# mmu6100.net
KiCad netlist of a schematic drawn in EAGLE
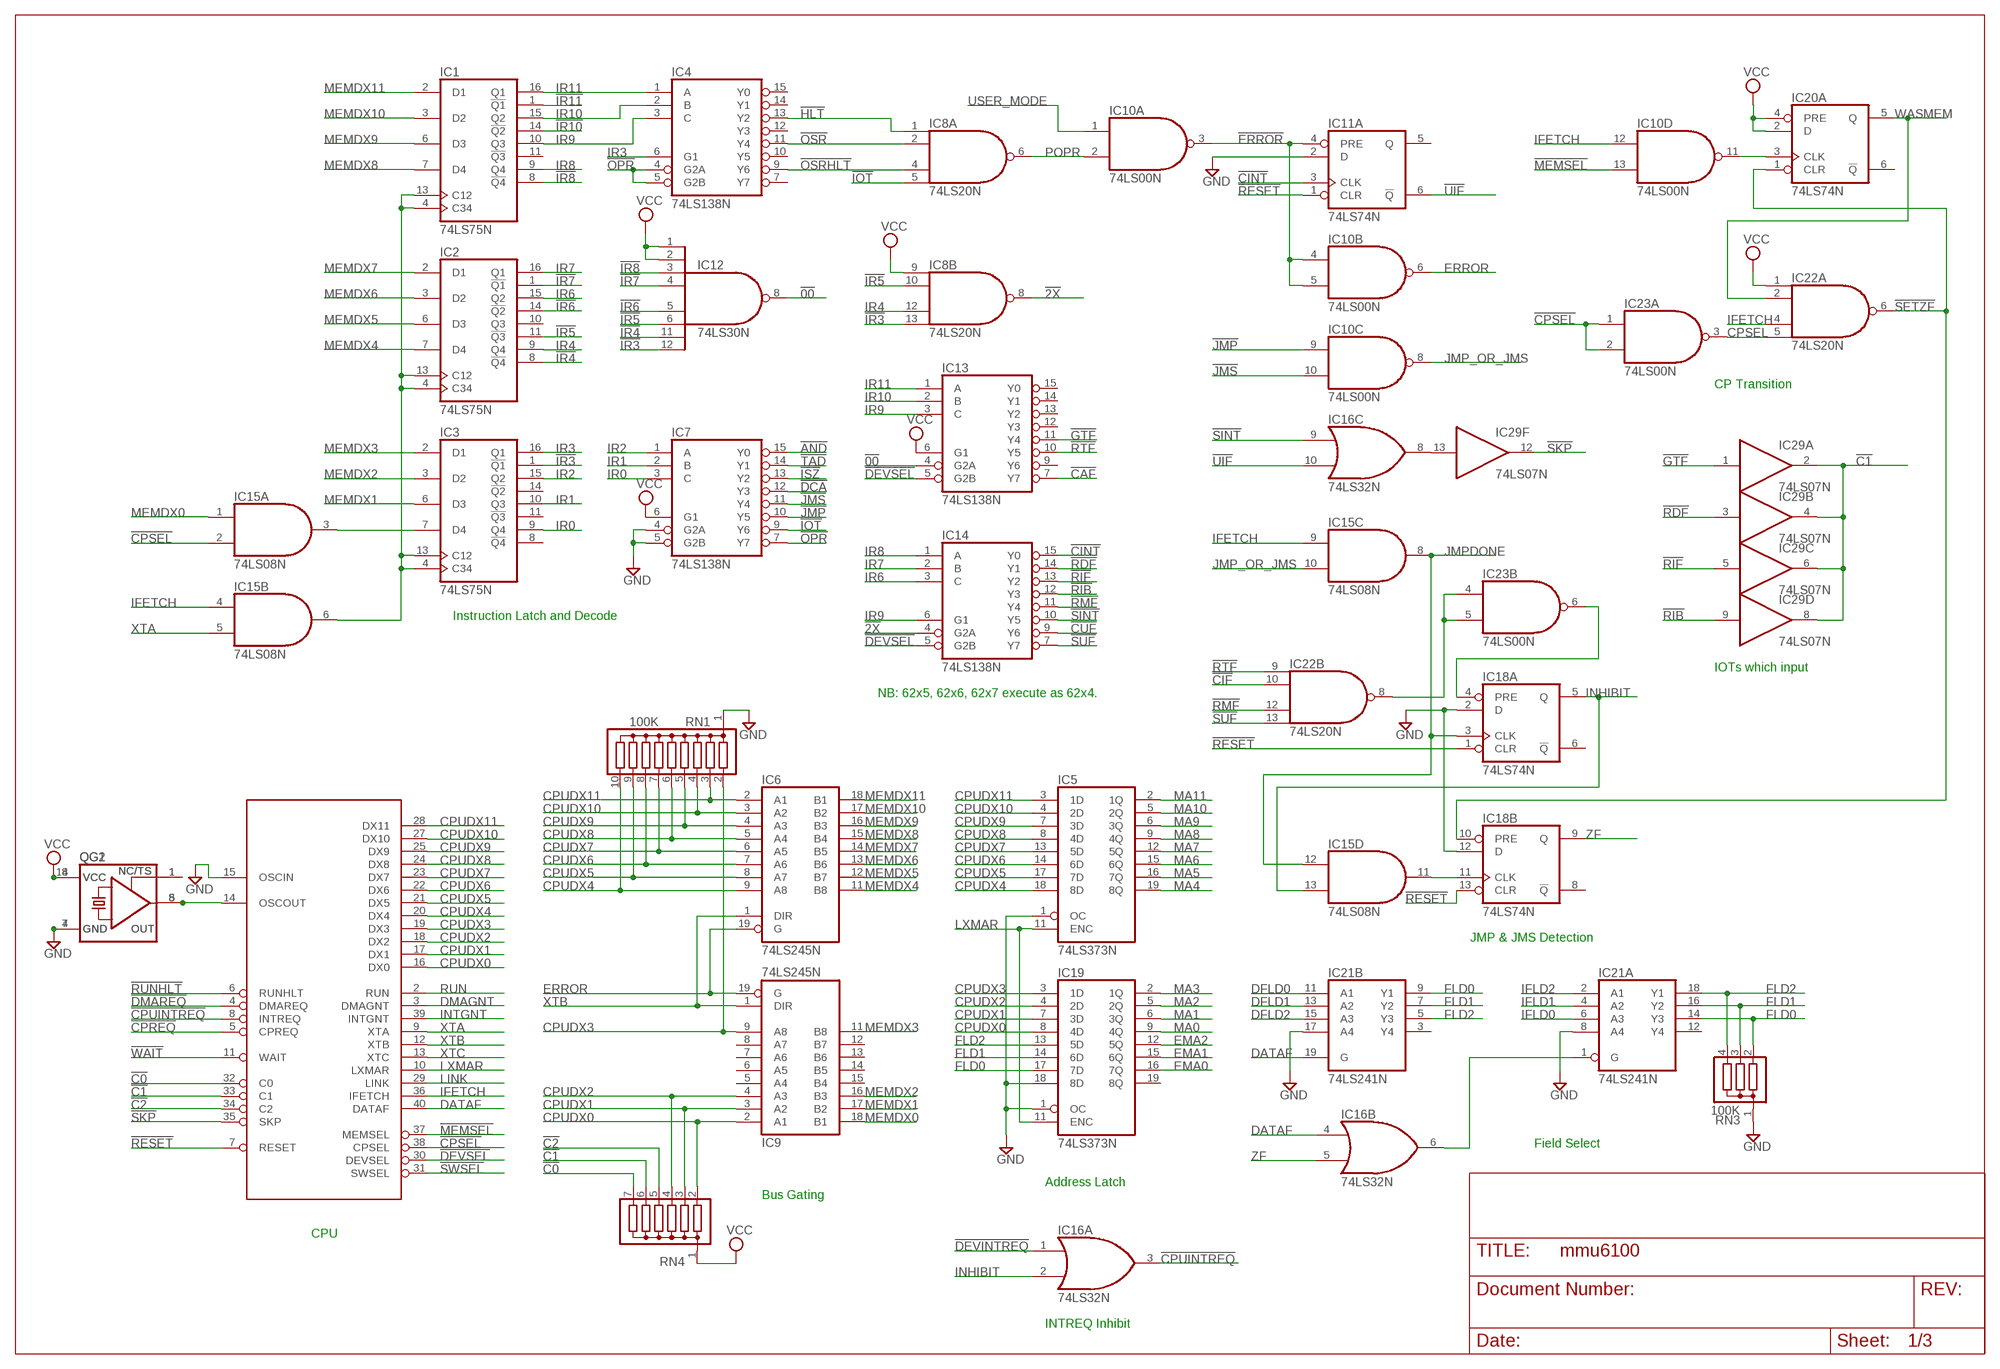
[diagram p0: schematic, sheet 1]
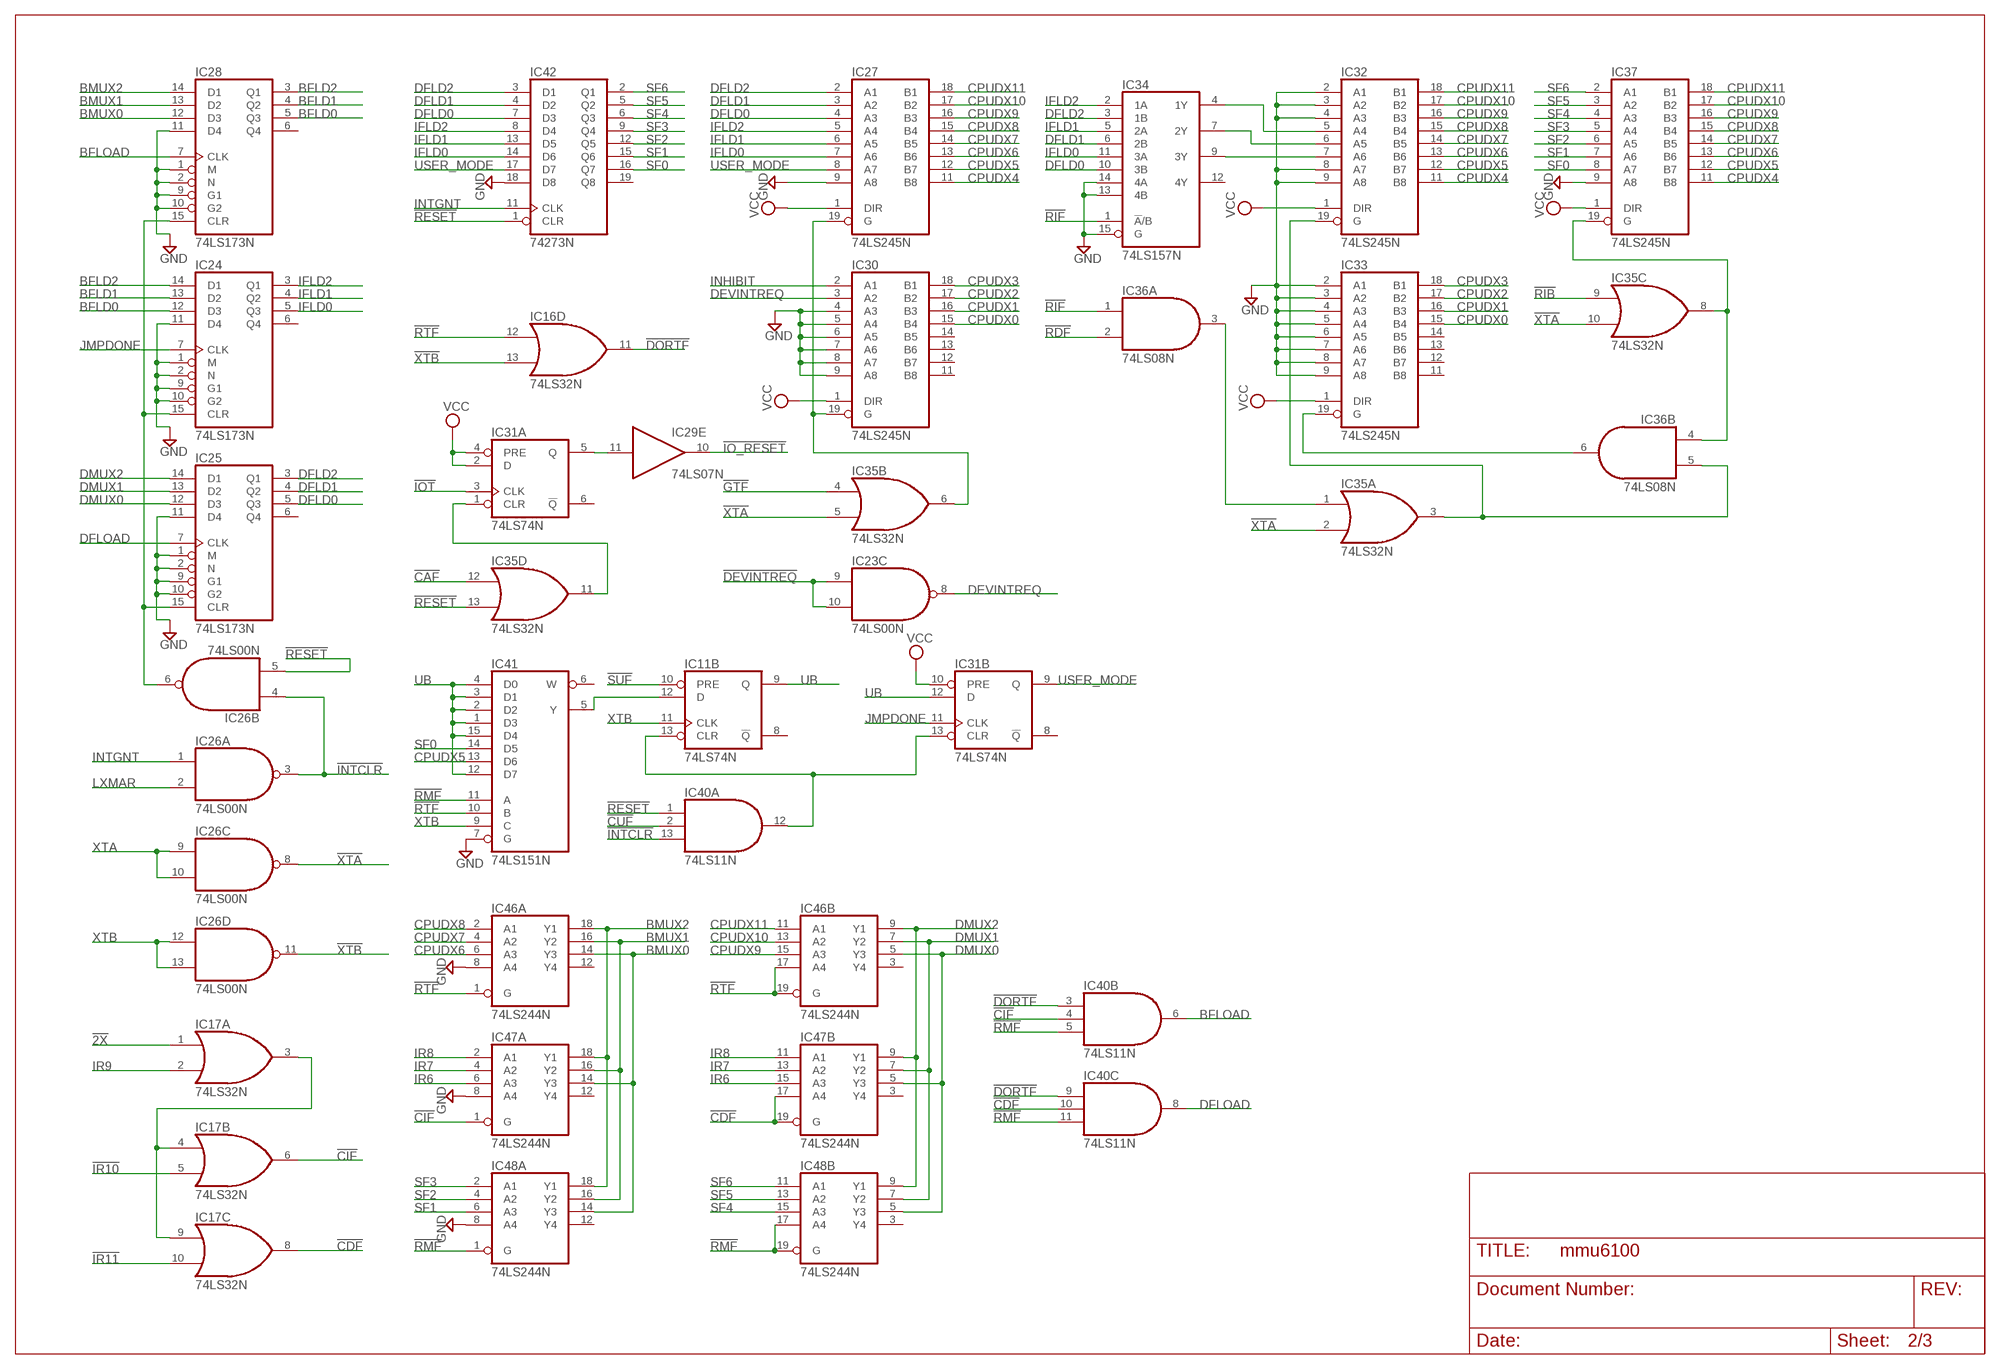
[diagram p1: schematic, sheet 2]
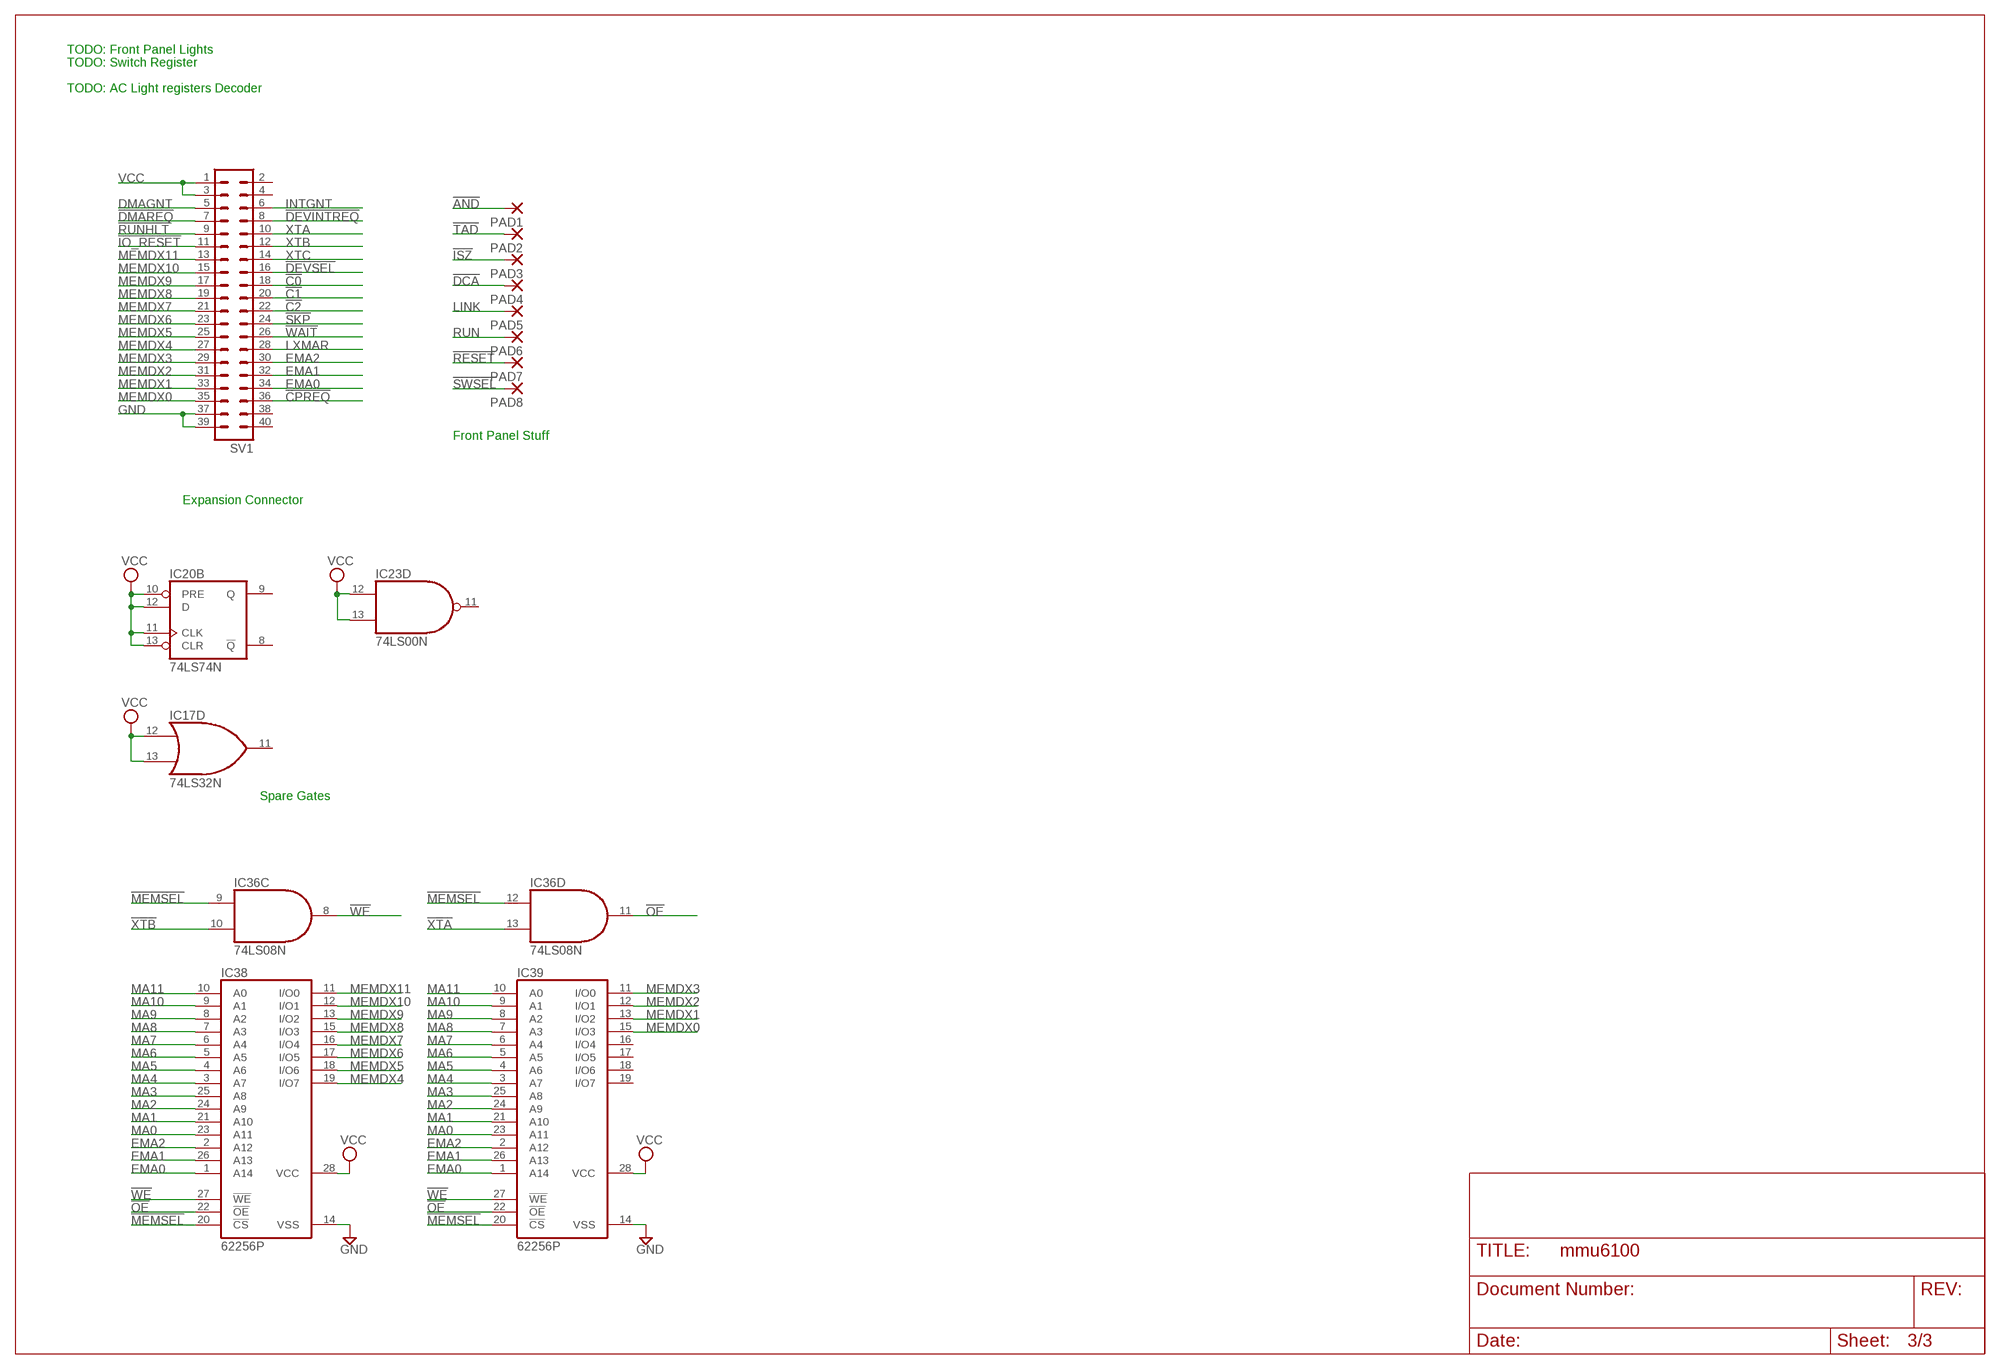
[diagram p2: schematic, sheet 3]

(export (version "E")
  (design (tool "Eeschema 10.0.6"))
  (components
    (comp (ref "IC17")
      (value "74LS32N")
      (footprint "eagle-import:DIL14")
      (libsource (lib "eagle-import") (part "7432NLS"))
    )
    (comp (ref "IC20")
      (value "74LS74N")
      (footprint "eagle-import:DIL14")
      (libsource (lib "eagle-import") (part "7474NLS"))
    )
    (comp (ref "IC23")
      (value "74LS00N")
      (footprint "eagle-import:DIL14")
      (libsource (lib "eagle-import") (part "7400NLS"))
    )
    (comp (ref "IC36")
      (value "74LS08N")
      (footprint "eagle-import:DIL14")
      (libsource (lib "eagle-import") (part "7408NLS"))
    )
    (comp (ref "IC38")
      (value "62256P")
      (footprint "eagle-import:DIL28-6")
      (libsource (lib "eagle-import") (part "62256P"))
    )
    (comp (ref "IC39")
      (value "62256P")
      (footprint "eagle-import:DIL28-6")
      (libsource (lib "eagle-import") (part "62256P"))
    )
    (comp (ref "PAD1")
      (value "2,15/1,0")
      (footprint "eagle-import:2,15_1,0")
      (libsource (lib "eagle-import") (part "2,15/1,0"))
    )
    (comp (ref "PAD2")
      (value "2,15/1,0")
      (footprint "eagle-import:2,15_1,0")
      (libsource (lib "eagle-import") (part "2,15/1,0"))
    )
    (comp (ref "PAD3")
      (value "2,15/1,0")
      (footprint "eagle-import:2,15_1,0")
      (libsource (lib "eagle-import") (part "2,15/1,0"))
    )
    (comp (ref "PAD4")
      (value "2,15/1,0")
      (footprint "eagle-import:2,15_1,0")
      (libsource (lib "eagle-import") (part "2,15/1,0"))
    )
    (comp (ref "PAD5")
      (value "2,15/1,0")
      (footprint "eagle-import:2,15_1,0")
      (libsource (lib "eagle-import") (part "2,15/1,0"))
    )
    (comp (ref "PAD6")
      (value "2,15/1,0")
      (footprint "eagle-import:2,15_1,0")
      (libsource (lib "eagle-import") (part "2,15/1,0"))
    )
    (comp (ref "PAD7")
      (value "2,15/1,0")
      (footprint "eagle-import:2,15_1,0")
      (libsource (lib "eagle-import") (part "2,15/1,0"))
    )
    (comp (ref "PAD8")
      (value "2,15/1,0")
      (footprint "eagle-import:2,15_1,0")
      (libsource (lib "eagle-import") (part "2,15/1,0"))
    )
    (comp (ref "SV1")
      (value "MA20-2")
      (footprint "eagle-import:MA20-2")
      (libsource (lib "eagle-import") (part "MA20-2"))
    )
    (comp (ref "IC11")
      (value "74LS74N")
      (footprint "eagle-import:DIL14")
      (libsource (lib "eagle-import") (part "7474NLS"))
    )
    (comp (ref "IC16")
      (value "74LS32N")
      (footprint "eagle-import:DIL14")
      (libsource (lib "eagle-import") (part "7432NLS"))
    )
    (comp (ref "IC24")
      (value "74LS173N")
      (footprint "eagle-import:DIL16")
      (libsource (lib "eagle-import") (part "74173NLS"))
    )
    (comp (ref "IC25")
      (value "74LS173N")
      (footprint "eagle-import:DIL16")
      (libsource (lib "eagle-import") (part "74173NLS"))
    )
    (comp (ref "IC26")
      (value "74LS00N")
      (footprint "eagle-import:DIL14")
      (libsource (lib "eagle-import") (part "7400NLS"))
    )
    (comp (ref "IC27")
      (value "74LS245N")
      (footprint "eagle-import:DIL20")
      (libsource (lib "eagle-import") (part "74245NLS"))
    )
    (comp (ref "IC28")
      (value "74LS173N")
      (footprint "eagle-import:DIL16")
      (libsource (lib "eagle-import") (part "74173NLS"))
    )
    (comp (ref "IC29")
      (value "74LS07N")
      (footprint "eagle-import:DIL14")
      (libsource (lib "eagle-import") (part "7407NLS"))
    )
    (comp (ref "IC30")
      (value "74LS245N")
      (footprint "eagle-import:DIL20")
      (libsource (lib "eagle-import") (part "74245NLS"))
    )
    (comp (ref "IC31")
      (value "74LS74N")
      (footprint "eagle-import:DIL14")
      (libsource (lib "eagle-import") (part "7474NLS"))
    )
    (comp (ref "IC32")
      (value "74LS245N")
      (footprint "eagle-import:DIL20")
      (libsource (lib "eagle-import") (part "74245NLS"))
    )
    (comp (ref "IC33")
      (value "74LS245N")
      (footprint "eagle-import:DIL20")
      (libsource (lib "eagle-import") (part "74245NLS"))
    )
    (comp (ref "IC34")
      (value "74LS157N")
      (footprint "eagle-import:DIL16")
      (libsource (lib "eagle-import") (part "74157NLS"))
    )
    (comp (ref "IC35")
      (value "74LS32N")
      (footprint "eagle-import:DIL14")
      (libsource (lib "eagle-import") (part "7432NLS"))
    )
    (comp (ref "IC37")
      (value "74LS245N")
      (footprint "eagle-import:DIL20")
      (libsource (lib "eagle-import") (part "74245NLS"))
    )
    (comp (ref "IC40")
      (value "74LS11N")
      (footprint "eagle-import:DIL14")
      (libsource (lib "eagle-import") (part "7411NLS"))
    )
    (comp (ref "IC41")
      (value "74LS151N")
      (footprint "eagle-import:DIL16")
      (libsource (lib "eagle-import") (part "74151NLS"))
    )
    (comp (ref "IC42")
      (value "74273N")
      (footprint "eagle-import:DIL20")
      (libsource (lib "eagle-import") (part "74273N"))
    )
    (comp (ref "IC46")
      (value "74LS244N")
      (footprint "eagle-import:DIL20")
      (libsource (lib "eagle-import") (part "74244NLS"))
    )
    (comp (ref "IC47")
      (value "74LS244N")
      (footprint "eagle-import:DIL20")
      (libsource (lib "eagle-import") (part "74244NLS"))
    )
    (comp (ref "IC48")
      (value "74LS244N")
      (footprint "eagle-import:DIL20")
      (libsource (lib "eagle-import") (part "74244NLS"))
    )
    (comp (ref "CPU")
      (value "IM6100")
      (footprint "eagle-import:DIL40")
      (libsource (lib "eagle-import") (part "IM6100"))
    )
    (comp (ref "IC1")
      (value "74LS75N")
      (footprint "eagle-import:DIL16")
      (libsource (lib "eagle-import") (part "7475NLS"))
    )
    (comp (ref "IC2")
      (value "74LS75N")
      (footprint "eagle-import:DIL16")
      (libsource (lib "eagle-import") (part "7475NLS"))
    )
    (comp (ref "IC3")
      (value "74LS75N")
      (footprint "eagle-import:DIL16")
      (libsource (lib "eagle-import") (part "7475NLS"))
    )
    (comp (ref "IC4")
      (value "74LS138N")
      (footprint "eagle-import:DIL16")
      (libsource (lib "eagle-import") (part "74138NLS"))
    )
    (comp (ref "IC5")
      (value "74LS373N")
      (footprint "eagle-import:DIL20")
      (libsource (lib "eagle-import") (part "74373NLS"))
    )
    (comp (ref "IC6")
      (value "74LS245N")
      (footprint "eagle-import:DIL20")
      (libsource (lib "eagle-import") (part "74245NLS"))
    )
    (comp (ref "IC7")
      (value "74LS138N")
      (footprint "eagle-import:DIL16")
      (libsource (lib "eagle-import") (part "74138NLS"))
    )
    (comp (ref "IC8")
      (value "74LS20N")
      (footprint "eagle-import:DIL14")
      (libsource (lib "eagle-import") (part "7420NLS"))
    )
    (comp (ref "IC9")
      (value "74LS245N")
      (footprint "eagle-import:DIL20")
      (libsource (lib "eagle-import") (part "74245NLS"))
    )
    (comp (ref "IC10")
      (value "74LS00N")
      (footprint "eagle-import:DIL14")
      (libsource (lib "eagle-import") (part "7400NLS"))
    )
    (comp (ref "IC12")
      (value "74LS30N")
      (footprint "eagle-import:DIL14")
      (libsource (lib "eagle-import") (part "7430NLS"))
    )
    (comp (ref "IC13")
      (value "74LS138N")
      (footprint "eagle-import:DIL16")
      (libsource (lib "eagle-import") (part "74138NLS"))
    )
    (comp (ref "IC14")
      (value "74LS138N")
      (footprint "eagle-import:DIL16")
      (libsource (lib "eagle-import") (part "74138NLS"))
    )
    (comp (ref "IC15")
      (value "74LS08N")
      (footprint "eagle-import:DIL14")
      (libsource (lib "eagle-import") (part "7408NLS"))
    )
    (comp (ref "IC18")
      (value "74LS74N")
      (footprint "eagle-import:DIL14")
      (libsource (lib "eagle-import") (part "7474NLS"))
    )
    (comp (ref "IC19")
      (value "74LS373N")
      (footprint "eagle-import:DIL20")
      (libsource (lib "eagle-import") (part "74373NLS"))
    )
    (comp (ref "IC21")
      (value "74LS241N")
      (footprint "eagle-import:DIL20")
      (libsource (lib "eagle-import") (part "74241NLS"))
    )
    (comp (ref "IC22")
      (value "74LS20N")
      (footprint "eagle-import:DIL14")
      (libsource (lib "eagle-import") (part "7420NLS"))
    )
    (comp (ref "QG1")
      (value "XO-8")
      (footprint "eagle-import:DIL08S")
      (libsource (lib "eagle-import") (part "XO-8"))
    )
    (comp (ref "QG2")
      (value "XO-14")
      (footprint "eagle-import:DIL14S")
      (libsource (lib "eagle-import") (part "XO-14"))
    )
    (comp (ref "RN1")
      (value "100K")
      (footprint "eagle-import:SIL10")
      (libsource (lib "eagle-import") (part "G09R"))
    )
    (comp (ref "RN3")
      (value "100K")
      (footprint "eagle-import:SIL4")
      (libsource (lib "eagle-import") (part "G03R"))
    )
    (comp (ref "RN4")
      (value "G06R")
      (footprint "eagle-import:SIL7")
      (libsource (lib "eagle-import") (part "G06R"))
    )
  )
  (nets
    (net (code "1") (name "BFLD0") (class "Default")
      (node (ref "IC24") (pin "12") (pinfunction "D3_12") (pintype "input"))
      (node (ref "IC28") (pin "5") (pinfunction "Q3_5") (pintype "tri_state"))
    )
    (net (code "2") (name "BFLD1") (class "Default")
      (node (ref "IC24") (pin "13") (pinfunction "D2_13") (pintype "input"))
      (node (ref "IC28") (pin "4") (pinfunction "Q2_4") (pintype "tri_state"))
    )
    (net (code "3") (name "BFLD2") (class "Default")
      (node (ref "IC24") (pin "14") (pinfunction "D1_14") (pintype "input"))
      (node (ref "IC28") (pin "3") (pinfunction "Q1_3") (pintype "tri_state"))
    )
    (net (code "4") (name "BFLOAD") (class "Default")
      (node (ref "IC28") (pin "7") (pinfunction "CLK_7") (pintype "input"))
      (node (ref "IC40") (pin "6") (pinfunction "O_6") (pintype "output"))
    )
    (net (code "5") (name "BMUX0") (class "Default")
      (node (ref "IC28") (pin "12") (pinfunction "D3_12") (pintype "input"))
      (node (ref "IC46") (pin "14") (pinfunction "Y3_14") (pintype "tri_state"))
      (node (ref "IC47") (pin "14") (pinfunction "Y3_14") (pintype "tri_state"))
      (node (ref "IC48") (pin "14") (pinfunction "Y3_14") (pintype "tri_state"))
    )
    (net (code "6") (name "BMUX1") (class "Default")
      (node (ref "IC28") (pin "13") (pinfunction "D2_13") (pintype "input"))
      (node (ref "IC46") (pin "16") (pinfunction "Y2_16") (pintype "tri_state"))
      (node (ref "IC47") (pin "16") (pinfunction "Y2_16") (pintype "tri_state"))
      (node (ref "IC48") (pin "16") (pinfunction "Y2_16") (pintype "tri_state"))
    )
    (net (code "7") (name "BMUX2") (class "Default")
      (node (ref "IC28") (pin "14") (pinfunction "D1_14") (pintype "input"))
      (node (ref "IC46") (pin "18") (pinfunction "Y1_18") (pintype "tri_state"))
      (node (ref "IC47") (pin "18") (pinfunction "Y1_18") (pintype "tri_state"))
      (node (ref "IC48") (pin "18") (pinfunction "Y1_18") (pintype "tri_state"))
    )
    (net (code "8") (name "CPSEL") (class "Default")
      (node (ref "IC22") (pin "5") (pinfunction "I3_5") (pintype "input"))
      (node (ref "IC23") (pin "3") (pinfunction "O_3") (pintype "output"))
    )
    (net (code "9") (name "CPUDX0") (class "Default")
      (node (ref "CPU") (pin "16") (pinfunction "DX0_16") (pintype "bidirectional"))
      (node (ref "IC19") (pin "8") (pinfunction "4D_8") (pintype "input"))
      (node (ref "IC30") (pin "15") (pinfunction "B4_15") (pintype "bidirectional"))
      (node (ref "IC33") (pin "15") (pinfunction "B4_15") (pintype "bidirectional"))
      (node (ref "IC9") (pin "2") (pinfunction "A1_2") (pintype "bidirectional"))
      (node (ref "RN4") (pin "2") (pinfunction "2_2") (pintype "passive"))
    )
    (net (code "10") (name "CPUDX1") (class "Default")
      (node (ref "CPU") (pin "17") (pinfunction "DX1_17") (pintype "bidirectional"))
      (node (ref "IC19") (pin "7") (pinfunction "3D_7") (pintype "input"))
      (node (ref "IC30") (pin "16") (pinfunction "B3_16") (pintype "bidirectional"))
      (node (ref "IC33") (pin "16") (pinfunction "B3_16") (pintype "bidirectional"))
      (node (ref "IC9") (pin "3") (pinfunction "A2_3") (pintype "bidirectional"))
      (node (ref "RN4") (pin "3") (pinfunction "3_3") (pintype "passive"))
    )
    (net (code "11") (name "CPUDX2") (class "Default")
      (node (ref "CPU") (pin "18") (pinfunction "DX2_18") (pintype "bidirectional"))
      (node (ref "IC19") (pin "4") (pinfunction "2D_4") (pintype "input"))
      (node (ref "IC30") (pin "17") (pinfunction "B2_17") (pintype "bidirectional"))
      (node (ref "IC33") (pin "17") (pinfunction "B2_17") (pintype "bidirectional"))
      (node (ref "IC9") (pin "4") (pinfunction "A3_4") (pintype "bidirectional"))
      (node (ref "RN4") (pin "4") (pinfunction "4_4") (pintype "passive"))
    )
    (net (code "12") (name "CPUDX3") (class "Default")
      (node (ref "CPU") (pin "19") (pinfunction "DX3_19") (pintype "bidirectional"))
      (node (ref "IC19") (pin "3") (pinfunction "1D_3") (pintype "input"))
      (node (ref "IC30") (pin "18") (pinfunction "B1_18") (pintype "bidirectional"))
      (node (ref "IC33") (pin "18") (pinfunction "B1_18") (pintype "bidirectional"))
      (node (ref "IC9") (pin "9") (pinfunction "A8_9") (pintype "bidirectional"))
      (node (ref "RN1") (pin "2") (pinfunction "2_2") (pintype "passive"))
    )
    (net (code "13") (name "CPUDX4") (class "Default")
      (node (ref "CPU") (pin "20") (pinfunction "DX4_20") (pintype "bidirectional"))
      (node (ref "IC27") (pin "11") (pinfunction "B8_11") (pintype "bidirectional"))
      (node (ref "IC32") (pin "11") (pinfunction "B8_11") (pintype "bidirectional"))
      (node (ref "IC37") (pin "11") (pinfunction "B8_11") (pintype "bidirectional"))
      (node (ref "IC5") (pin "18") (pinfunction "8D_18") (pintype "input"))
      (node (ref "IC6") (pin "9") (pinfunction "A8_9") (pintype "bidirectional"))
      (node (ref "RN1") (pin "10") (pinfunction "10_10") (pintype "passive"))
    )
    (net (code "14") (name "CPUDX5") (class "Default")
      (node (ref "CPU") (pin "21") (pinfunction "DX5_21") (pintype "bidirectional"))
      (node (ref "IC27") (pin "12") (pinfunction "B7_12") (pintype "bidirectional"))
      (node (ref "IC32") (pin "12") (pinfunction "B7_12") (pintype "bidirectional"))
      (node (ref "IC37") (pin "12") (pinfunction "B7_12") (pintype "bidirectional"))
      (node (ref "IC41") (pin "13") (pinfunction "D6_13") (pintype "input"))
      (node (ref "IC5") (pin "17") (pinfunction "7D_17") (pintype "input"))
      (node (ref "IC6") (pin "8") (pinfunction "A7_8") (pintype "bidirectional"))
      (node (ref "RN1") (pin "9") (pinfunction "9_9") (pintype "passive"))
    )
    (net (code "15") (name "CPUDX6") (class "Default")
      (node (ref "CPU") (pin "22") (pinfunction "DX6_22") (pintype "bidirectional"))
      (node (ref "IC27") (pin "13") (pinfunction "B6_13") (pintype "bidirectional"))
      (node (ref "IC32") (pin "13") (pinfunction "B6_13") (pintype "bidirectional"))
      (node (ref "IC37") (pin "13") (pinfunction "B6_13") (pintype "bidirectional"))
      (node (ref "IC46") (pin "6") (pinfunction "A3_6") (pintype "input"))
      (node (ref "IC5") (pin "14") (pinfunction "6D_14") (pintype "input"))
      (node (ref "IC6") (pin "7") (pinfunction "A6_7") (pintype "bidirectional"))
      (node (ref "RN1") (pin "8") (pinfunction "8_8") (pintype "passive"))
    )
    (net (code "16") (name "CPUDX7") (class "Default")
      (node (ref "CPU") (pin "23") (pinfunction "DX7_23") (pintype "bidirectional"))
      (node (ref "IC27") (pin "14") (pinfunction "B5_14") (pintype "bidirectional"))
      (node (ref "IC32") (pin "14") (pinfunction "B5_14") (pintype "bidirectional"))
      (node (ref "IC37") (pin "14") (pinfunction "B5_14") (pintype "bidirectional"))
      (node (ref "IC46") (pin "4") (pinfunction "A2_4") (pintype "input"))
      (node (ref "IC5") (pin "13") (pinfunction "5D_13") (pintype "input"))
      (node (ref "IC6") (pin "6") (pinfunction "A5_6") (pintype "bidirectional"))
      (node (ref "RN1") (pin "7") (pinfunction "7_7") (pintype "passive"))
    )
    (net (code "17") (name "CPUDX8") (class "Default")
      (node (ref "CPU") (pin "24") (pinfunction "DX8_24") (pintype "bidirectional"))
      (node (ref "IC27") (pin "15") (pinfunction "B4_15") (pintype "bidirectional"))
      (node (ref "IC32") (pin "15") (pinfunction "B4_15") (pintype "bidirectional"))
      (node (ref "IC37") (pin "15") (pinfunction "B4_15") (pintype "bidirectional"))
      (node (ref "IC46") (pin "2") (pinfunction "A1_2") (pintype "input"))
      (node (ref "IC5") (pin "8") (pinfunction "4D_8") (pintype "input"))
      (node (ref "IC6") (pin "5") (pinfunction "A4_5") (pintype "bidirectional"))
      (node (ref "RN1") (pin "6") (pinfunction "6_6") (pintype "passive"))
    )
    (net (code "18") (name "CPUDX9") (class "Default")
      (node (ref "CPU") (pin "25") (pinfunction "DX9_25") (pintype "bidirectional"))
      (node (ref "IC27") (pin "16") (pinfunction "B3_16") (pintype "bidirectional"))
      (node (ref "IC32") (pin "16") (pinfunction "B3_16") (pintype "bidirectional"))
      (node (ref "IC37") (pin "16") (pinfunction "B3_16") (pintype "bidirectional"))
      (node (ref "IC46") (pin "15") (pinfunction "A3_15") (pintype "input"))
      (node (ref "IC5") (pin "7") (pinfunction "3D_7") (pintype "input"))
      (node (ref "IC6") (pin "4") (pinfunction "A3_4") (pintype "bidirectional"))
      (node (ref "RN1") (pin "5") (pinfunction "5_5") (pintype "passive"))
    )
    (net (code "19") (name "CPUDX10") (class "Default")
      (node (ref "CPU") (pin "27") (pinfunction "DX10_27") (pintype "bidirectional"))
      (node (ref "IC27") (pin "17") (pinfunction "B2_17") (pintype "bidirectional"))
      (node (ref "IC32") (pin "17") (pinfunction "B2_17") (pintype "bidirectional"))
      (node (ref "IC37") (pin "17") (pinfunction "B2_17") (pintype "bidirectional"))
      (node (ref "IC46") (pin "13") (pinfunction "A2_13") (pintype "input"))
      (node (ref "IC5") (pin "4") (pinfunction "2D_4") (pintype "input"))
      (node (ref "IC6") (pin "3") (pinfunction "A2_3") (pintype "bidirectional"))
      (node (ref "RN1") (pin "4") (pinfunction "4_4") (pintype "passive"))
    )
    (net (code "20") (name "CPUDX11") (class "Default")
      (node (ref "CPU") (pin "28") (pinfunction "DX11_28") (pintype "bidirectional"))
      (node (ref "IC27") (pin "18") (pinfunction "B1_18") (pintype "bidirectional"))
      (node (ref "IC32") (pin "18") (pinfunction "B1_18") (pintype "bidirectional"))
      (node (ref "IC37") (pin "18") (pinfunction "B1_18") (pintype "bidirectional"))
      (node (ref "IC46") (pin "11") (pinfunction "A1_11") (pintype "input"))
      (node (ref "IC5") (pin "3") (pinfunction "1D_3") (pintype "input"))
      (node (ref "IC6") (pin "2") (pinfunction "A1_2") (pintype "bidirectional"))
      (node (ref "RN1") (pin "3") (pinfunction "3_3") (pintype "passive"))
    )
    (net (code "21") (name "DATAF") (class "Default")
      (node (ref "CPU") (pin "40") (pinfunction "DATAF_40") (pintype "output"))
      (node (ref "IC16") (pin "4") (pinfunction "I0_4") (pintype "input"))
      (node (ref "IC21") (pin "19") (pinfunction "G_19") (pintype "input"))
    )
    (net (code "22") (name "DEVINTREQ") (class "Default")
      (node (ref "IC23") (pin "8") (pinfunction "O_8") (pintype "output"))
      (node (ref "IC30") (pin "3") (pinfunction "A2_3") (pintype "bidirectional"))
    )
    (net (code "23") (name "DFLD0") (class "Default")
      (node (ref "IC21") (pin "11") (pinfunction "A1_11") (pintype "input"))
      (node (ref "IC25") (pin "5") (pinfunction "Q3_5") (pintype "tri_state"))
      (node (ref "IC27") (pin "4") (pinfunction "A3_4") (pintype "bidirectional"))
      (node (ref "IC34") (pin "10") (pinfunction "3B_10") (pintype "input"))
      (node (ref "IC42") (pin "7") (pinfunction "D3_7") (pintype "input"))
    )
    (net (code "24") (name "DFLD1") (class "Default")
      (node (ref "IC21") (pin "13") (pinfunction "A2_13") (pintype "input"))
      (node (ref "IC25") (pin "4") (pinfunction "Q2_4") (pintype "tri_state"))
      (node (ref "IC27") (pin "3") (pinfunction "A2_3") (pintype "bidirectional"))
      (node (ref "IC34") (pin "6") (pinfunction "2B_6") (pintype "input"))
      (node (ref "IC42") (pin "4") (pinfunction "D2_4") (pintype "input"))
    )
    (net (code "25") (name "DFLD2") (class "Default")
      (node (ref "IC21") (pin "15") (pinfunction "A3_15") (pintype "input"))
      (node (ref "IC25") (pin "3") (pinfunction "Q1_3") (pintype "tri_state"))
      (node (ref "IC27") (pin "2") (pinfunction "A1_2") (pintype "bidirectional"))
      (node (ref "IC34") (pin "3") (pinfunction "1B_3") (pintype "input"))
      (node (ref "IC42") (pin "3") (pinfunction "D1_3") (pintype "input"))
    )
    (net (code "26") (name "DFLOAD") (class "Default")
      (node (ref "IC25") (pin "7") (pinfunction "CLK_7") (pintype "input"))
      (node (ref "IC40") (pin "8") (pinfunction "O_8") (pintype "output"))
    )
    (net (code "27") (name "DMAGNT") (class "Default")
      (node (ref "CPU") (pin "3") (pinfunction "DMAGNT_3") (pintype "output"))
      (node (ref "SV1") (pin "5") (pinfunction "5_5") (pintype "passive"))
    )
    (net (code "28") (name "DMUX0") (class "Default")
      (node (ref "IC25") (pin "12") (pinfunction "D3_12") (pintype "input"))
      (node (ref "IC46") (pin "5") (pinfunction "Y3_5") (pintype "tri_state"))
      (node (ref "IC47") (pin "5") (pinfunction "Y3_5") (pintype "tri_state"))
      (node (ref "IC48") (pin "5") (pinfunction "Y3_5") (pintype "tri_state"))
    )
    (net (code "29") (name "DMUX1") (class "Default")
      (node (ref "IC25") (pin "13") (pinfunction "D2_13") (pintype "input"))
      (node (ref "IC46") (pin "7") (pinfunction "Y2_7") (pintype "tri_state"))
      (node (ref "IC47") (pin "7") (pinfunction "Y2_7") (pintype "tri_state"))
      (node (ref "IC48") (pin "7") (pinfunction "Y2_7") (pintype "tri_state"))
    )
    (net (code "30") (name "DMUX2") (class "Default")
      (node (ref "IC25") (pin "14") (pinfunction "D1_14") (pintype "input"))
      (node (ref "IC46") (pin "9") (pinfunction "Y1_9") (pintype "tri_state"))
      (node (ref "IC47") (pin "9") (pinfunction "Y1_9") (pintype "tri_state"))
      (node (ref "IC48") (pin "9") (pinfunction "Y1_9") (pintype "tri_state"))
    )
    (net (code "31") (name "EMA0") (class "Default")
      (node (ref "IC19") (pin "16") (pinfunction "7Q_16") (pintype "tri_state"))
      (node (ref "IC38") (pin "1") (pinfunction "A14_1") (pintype "input"))
      (node (ref "IC39") (pin "1") (pinfunction "A14_1") (pintype "input"))
      (node (ref "SV1") (pin "34") (pinfunction "34_34") (pintype "passive"))
    )
    (net (code "32") (name "EMA1") (class "Default")
      (node (ref "IC19") (pin "15") (pinfunction "6Q_15") (pintype "tri_state"))
      (node (ref "IC38") (pin "26") (pinfunction "A13_26") (pintype "input"))
      (node (ref "IC39") (pin "26") (pinfunction "A13_26") (pintype "input"))
      (node (ref "SV1") (pin "32") (pinfunction "32_32") (pintype "passive"))
    )
    (net (code "33") (name "EMA2") (class "Default")
      (node (ref "IC19") (pin "12") (pinfunction "5Q_12") (pintype "tri_state"))
      (node (ref "IC38") (pin "2") (pinfunction "A12_2") (pintype "input"))
      (node (ref "IC39") (pin "2") (pinfunction "A12_2") (pintype "input"))
      (node (ref "SV1") (pin "30") (pinfunction "30_30") (pintype "passive"))
    )
    (net (code "34") (name "ERROR") (class "Default")
      (node (ref "IC10") (pin "6") (pinfunction "O_6") (pintype "output"))
      (node (ref "IC6") (pin "19") (pinfunction "G_19") (pintype "input"))
      (node (ref "IC9") (pin "19") (pinfunction "G_19") (pintype "input"))
    )
    (net (code "35") (name "FLD0") (class "Default")
      (node (ref "IC19") (pin "17") (pinfunction "7D_17") (pintype "input"))
      (node (ref "IC21") (pin "14") (pinfunction "Y3_14") (pintype "tri_state"))
      (node (ref "IC21") (pin "9") (pinfunction "Y1_9") (pintype "tri_state"))
      (node (ref "RN3") (pin "2") (pinfunction "2_2") (pintype "passive"))
    )
    (net (code "36") (name "FLD1") (class "Default")
      (node (ref "IC19") (pin "14") (pinfunction "6D_14") (pintype "input"))
      (node (ref "IC21") (pin "16") (pinfunction "Y2_16") (pintype "tri_state"))
      (node (ref "IC21") (pin "7") (pinfunction "Y2_7") (pintype "tri_state"))
      (node (ref "RN3") (pin "3") (pinfunction "3_3") (pintype "passive"))
    )
    (net (code "37") (name "FLD2") (class "Default")
      (node (ref "IC19") (pin "13") (pinfunction "5D_13") (pintype "input"))
      (node (ref "IC21") (pin "18") (pinfunction "Y1_18") (pintype "tri_state"))
      (node (ref "IC21") (pin "5") (pinfunction "Y3_5") (pintype "tri_state"))
      (node (ref "RN3") (pin "4") (pinfunction "4_4") (pintype "passive"))
    )
    (net (code "38") (name "GND") (class "Default")
      (node (ref "CPU") (pin "15") (pinfunction "OSCIN_15") (pintype "input"))
      (node (ref "IC11") (pin "2") (pinfunction "D_2") (pintype "input"))
      (node (ref "IC18") (pin "12") (pinfunction "D_12") (pintype "input"))
      (node (ref "IC18") (pin "2") (pinfunction "D_2") (pintype "input"))
      (node (ref "IC19") (pin "1") (pinfunction "OC_1") (pintype "input"))
      (node (ref "IC19") (pin "18") (pinfunction "8D_18") (pintype "input"))
      (node (ref "IC21") (pin "17") (pinfunction "A4_17") (pintype "input"))
      (node (ref "IC21") (pin "8") (pinfunction "A4_8") (pintype "input"))
      (node (ref "IC24") (pin "1") (pinfunction "M_1") (pintype "input"))
      (node (ref "IC24") (pin "10") (pinfunction "G2_10") (pintype "input"))
      (node (ref "IC24") (pin "11") (pinfunction "D4_11") (pintype "input"))
      (node (ref "IC24") (pin "2") (pinfunction "N_2") (pintype "input"))
      (node (ref "IC24") (pin "9") (pinfunction "G1_9") (pintype "input"))
      (node (ref "IC25") (pin "1") (pinfunction "M_1") (pintype "input"))
      (node (ref "IC25") (pin "10") (pinfunction "G2_10") (pintype "input"))
      (node (ref "IC25") (pin "11") (pinfunction "D4_11") (pintype "input"))
      (node (ref "IC25") (pin "2") (pinfunction "N_2") (pintype "input"))
      (node (ref "IC25") (pin "9") (pinfunction "G1_9") (pintype "input"))
      (node (ref "IC27") (pin "9") (pinfunction "A8_9") (pintype "bidirectional"))
      (node (ref "IC28") (pin "1") (pinfunction "M_1") (pintype "input"))
      (node (ref "IC28") (pin "10") (pinfunction "G2_10") (pintype "input"))
      (node (ref "IC28") (pin "11") (pinfunction "D4_11") (pintype "input"))
      (node (ref "IC28") (pin "2") (pinfunction "N_2") (pintype "input"))
      (node (ref "IC28") (pin "9") (pinfunction "G1_9") (pintype "input"))
      (node (ref "IC30") (pin "4") (pinfunction "A3_4") (pintype "bidirectional"))
      (node (ref "IC30") (pin "5") (pinfunction "A4_5") (pintype "bidirectional"))
      (node (ref "IC30") (pin "6") (pinfunction "A5_6") (pintype "bidirectional"))
      (node (ref "IC30") (pin "7") (pinfunction "A6_7") (pintype "bidirectional"))
      (node (ref "IC30") (pin "8") (pinfunction "A7_8") (pintype "bidirectional"))
      (node (ref "IC30") (pin "9") (pinfunction "A8_9") (pintype "bidirectional"))
      (node (ref "IC32") (pin "2") (pinfunction "A1_2") (pintype "bidirectional"))
      (node (ref "IC32") (pin "3") (pinfunction "A2_3") (pintype "bidirectional"))
      (node (ref "IC32") (pin "4") (pinfunction "A3_4") (pintype "bidirectional"))
      (node (ref "IC32") (pin "8") (pinfunction "A7_8") (pintype "bidirectional"))
      (node (ref "IC32") (pin "9") (pinfunction "A8_9") (pintype "bidirectional"))
      (node (ref "IC33") (pin "2") (pinfunction "A1_2") (pintype "bidirectional"))
      (node (ref "IC33") (pin "3") (pinfunction "A2_3") (pintype "bidirectional"))
      (node (ref "IC33") (pin "4") (pinfunction "A3_4") (pintype "bidirectional"))
      (node (ref "IC33") (pin "5") (pinfunction "A4_5") (pintype "bidirectional"))
      (node (ref "IC33") (pin "6") (pinfunction "A5_6") (pintype "bidirectional"))
      (node (ref "IC33") (pin "7") (pinfunction "A6_7") (pintype "bidirectional"))
      (node (ref "IC33") (pin "8") (pinfunction "A7_8") (pintype "bidirectional"))
      (node (ref "IC33") (pin "9") (pinfunction "A8_9") (pintype "bidirectional"))
      (node (ref "IC34") (pin "13") (pinfunction "4B_13") (pintype "input"))
      (node (ref "IC34") (pin "14") (pinfunction "4A_14") (pintype "input"))
      (node (ref "IC34") (pin "15") (pinfunction "G_15") (pintype "input"))
      (node (ref "IC37") (pin "9") (pinfunction "A8_9") (pintype "bidirectional"))
      (node (ref "IC38") (pin "14") (pinfunction "VSS_14") (pintype "power_in"))
      (node (ref "IC39") (pin "14") (pinfunction "VSS_14") (pintype "power_in"))
      (node (ref "IC41") (pin "7") (pinfunction "G_7") (pintype "input"))
      (node (ref "IC42") (pin "18") (pinfunction "D8_18") (pintype "input"))
      (node (ref "IC46") (pin "8") (pinfunction "A4_8") (pintype "input"))
      (node (ref "IC47") (pin "8") (pinfunction "A4_8") (pintype "input"))
      (node (ref "IC48") (pin "8") (pinfunction "A4_8") (pintype "input"))
      (node (ref "IC5") (pin "1") (pinfunction "OC_1") (pintype "input"))
      (node (ref "IC7") (pin "4") (pinfunction "G2A_4") (pintype "input"))
      (node (ref "IC7") (pin "5") (pinfunction "G2B_5") (pintype "input"))
      (node (ref "QG1") (pin "4") (pinfunction "GND_4") (pintype "power_in"))
      (node (ref "QG2") (pin "7") (pinfunction "GND_7") (pintype "power_in"))
      (node (ref "RN1") (pin "1") (pinfunction "1_1") (pintype "passive"))
      (node (ref "RN3") (pin "1") (pinfunction "1_1") (pintype "passive"))
      (node (ref "SV1") (pin "37") (pinfunction "37_37") (pintype "passive"))
      (node (ref "SV1") (pin "39") (pinfunction "39_39") (pintype "passive"))
    )
    (net (code "39") (name "IFETCH") (class "Default")
      (node (ref "CPU") (pin "36") (pinfunction "IFETCH_36") (pintype "output"))
      (node (ref "IC10") (pin "12") (pinfunction "I0_12") (pintype "input"))
      (node (ref "IC15") (pin "4") (pinfunction "I0_4") (pintype "input"))
      (node (ref "IC15") (pin "9") (pinfunction "I0_9") (pintype "input"))
      (node (ref "IC22") (pin "4") (pinfunction "I2_4") (pintype "input"))
    )
    (net (code "40") (name "IFLD0") (class "Default")
      (node (ref "IC21") (pin "6") (pinfunction "A3_6") (pintype "input"))
      (node (ref "IC24") (pin "5") (pinfunction "Q3_5") (pintype "tri_state"))
      (node (ref "IC27") (pin "7") (pinfunction "A6_7") (pintype "bidirectional"))
      (node (ref "IC34") (pin "11") (pinfunction "3A_11") (pintype "input"))
      (node (ref "IC42") (pin "14") (pinfunction "D6_14") (pintype "input"))
    )
    (net (code "41") (name "IFLD1") (class "Default")
      (node (ref "IC21") (pin "4") (pinfunction "A2_4") (pintype "input"))
      (node (ref "IC24") (pin "4") (pinfunction "Q2_4") (pintype "tri_state"))
      (node (ref "IC27") (pin "6") (pinfunction "A5_6") (pintype "bidirectional"))
      (node (ref "IC34") (pin "5") (pinfunction "2A_5") (pintype "input"))
      (node (ref "IC42") (pin "13") (pinfunction "D5_13") (pintype "input"))
    )
    (net (code "42") (name "IFLD2") (class "Default")
      (node (ref "IC21") (pin "2") (pinfunction "A1_2") (pintype "input"))
      (node (ref "IC24") (pin "3") (pinfunction "Q1_3") (pintype "tri_state"))
      (node (ref "IC27") (pin "5") (pinfunction "A4_5") (pintype "bidirectional"))
      (node (ref "IC34") (pin "2") (pinfunction "1A_2") (pintype "input"))
      (node (ref "IC42") (pin "8") (pinfunction "D4_8") (pintype "input"))
    )
    (net (code "43") (name "INHIBIT") (class "Default")
      (node (ref "IC15") (pin "13") (pinfunction "I1_13") (pintype "input"))
      (node (ref "IC16") (pin "2") (pinfunction "I1_2") (pintype "input"))
      (node (ref "IC18") (pin "5") (pinfunction "Q_5") (pintype "output"))
      (node (ref "IC30") (pin "2") (pinfunction "A1_2") (pintype "bidirectional"))
    )
    (net (code "44") (name "INTGNT") (class "Default")
      (node (ref "CPU") (pin "39") (pinfunction "INTGNT_39") (pintype "output"))
      (node (ref "IC26") (pin "1") (pinfunction "I0_1") (pintype "input"))
      (node (ref "IC42") (pin "11") (pinfunction "CLK_11") (pintype "input"))
      (node (ref "SV1") (pin "6") (pinfunction "6_6") (pintype "passive"))
    )
    (net (code "45") (name "IR0") (class "Default")
      (node (ref "IC3") (pin "9") (pinfunction "Q4_9") (pintype "output"))
      (node (ref "IC7") (pin "3") (pinfunction "C_3") (pintype "input"))
    )
    (net (code "46") (name "IR1") (class "Default")
      (node (ref "IC3") (pin "10") (pinfunction "Q3_10") (pintype "output"))
      (node (ref "IC7") (pin "2") (pinfunction "B_2") (pintype "input"))
    )
    (net (code "47") (name "IR2") (class "Default")
      (node (ref "IC3") (pin "15") (pinfunction "Q2_15") (pintype "output"))
      (node (ref "IC7") (pin "1") (pinfunction "A_1") (pintype "input"))
    )
    (net (code "48") (name "IR3") (class "Default")
      (node (ref "IC3") (pin "16") (pinfunction "Q1_16") (pintype "output"))
      (node (ref "IC4") (pin "6") (pinfunction "G1_6") (pintype "input"))
    )
    (net (code "49") (name "IR4") (class "Default")
      (node (ref "IC2") (pin "9") (pinfunction "Q4_9") (pintype "output"))
      (node (ref "IC8") (pin "12") (pinfunction "I2_12") (pintype "input"))
    )
    (net (code "50") (name "IR6") (class "Default")
      (node (ref "IC14") (pin "3") (pinfunction "C_3") (pintype "input"))
      (node (ref "IC2") (pin "15") (pinfunction "Q2_15") (pintype "output"))
      (node (ref "IC47") (pin "15") (pinfunction "A3_15") (pintype "input"))
      (node (ref "IC47") (pin "6") (pinfunction "A3_6") (pintype "input"))
    )
    (net (code "51") (name "IR7") (class "Default")
      (node (ref "IC14") (pin "2") (pinfunction "B_2") (pintype "input"))
      (node (ref "IC2") (pin "16") (pinfunction "Q1_16") (pintype "output"))
      (node (ref "IC47") (pin "13") (pinfunction "A2_13") (pintype "input"))
      (node (ref "IC47") (pin "4") (pinfunction "A2_4") (pintype "input"))
    )
    (net (code "52") (name "IR8") (class "Default")
      (node (ref "IC1") (pin "9") (pinfunction "Q4_9") (pintype "output"))
      (node (ref "IC14") (pin "1") (pinfunction "A_1") (pintype "input"))
      (node (ref "IC47") (pin "11") (pinfunction "A1_11") (pintype "input"))
      (node (ref "IC47") (pin "2") (pinfunction "A1_2") (pintype "input"))
    )
    (net (code "53") (name "IR9") (class "Default")
      (node (ref "IC1") (pin "10") (pinfunction "Q3_10") (pintype "output"))
      (node (ref "IC13") (pin "3") (pinfunction "C_3") (pintype "input"))
      (node (ref "IC14") (pin "6") (pinfunction "G1_6") (pintype "input"))
      (node (ref "IC17") (pin "2") (pinfunction "I1_2") (pintype "input"))
      (node (ref "IC4") (pin "3") (pinfunction "C_3") (pintype "input"))
    )
    (net (code "54") (name "IR10") (class "Default")
      (node (ref "IC1") (pin "15") (pinfunction "Q2_15") (pintype "output"))
      (node (ref "IC13") (pin "2") (pinfunction "B_2") (pintype "input"))
      (node (ref "IC4") (pin "2") (pinfunction "B_2") (pintype "input"))
    )
    (net (code "55") (name "IR11") (class "Default")
      (node (ref "IC1") (pin "16") (pinfunction "Q1_16") (pintype "output"))
      (node (ref "IC13") (pin "1") (pinfunction "A_1") (pintype "input"))
      (node (ref "IC4") (pin "1") (pinfunction "A_1") (pintype "input"))
    )
    (net (code "56") (name "JMPDONE") (class "Default")
      (node (ref "IC15") (pin "12") (pinfunction "I0_12") (pintype "input"))
      (node (ref "IC15") (pin "8") (pinfunction "O_8") (pintype "output"))
      (node (ref "IC18") (pin "3") (pinfunction "CLK_3") (pintype "input"))
      (node (ref "IC24") (pin "7") (pinfunction "CLK_7") (pintype "input"))
      (node (ref "IC31") (pin "11") (pinfunction "CLK_11") (pintype "input"))
    )
    (net (code "57") (name "JMP_OR_JMS") (class "Default")
      (node (ref "IC10") (pin "8") (pinfunction "O_8") (pintype "output"))
      (node (ref "IC15") (pin "10") (pinfunction "I1_10") (pintype "input"))
    )
    (net (code "58") (name "LINK") (class "Default")
      (node (ref "CPU") (pin "29") (pinfunction "LINK_29") (pintype "output"))
      (node (ref "PAD5") (pin "1") (pinfunction "P_1") (pintype "passive"))
    )
    (net (code "59") (name "LXMAR") (class "Default")
      (node (ref "CPU") (pin "10") (pinfunction "LXMAR_10") (pintype "output"))
      (node (ref "IC19") (pin "11") (pinfunction "ENC_11") (pintype "input"))
      (node (ref "IC26") (pin "2") (pinfunction "I1_2") (pintype "input"))
      (node (ref "IC5") (pin "11") (pinfunction "ENC_11") (pintype "input"))
      (node (ref "SV1") (pin "28") (pinfunction "28_28") (pintype "passive"))
    )
    (net (code "60") (name "MA0") (class "Default")
      (node (ref "IC19") (pin "9") (pinfunction "4Q_9") (pintype "tri_state"))
      (node (ref "IC38") (pin "23") (pinfunction "A11_23") (pintype "input"))
      (node (ref "IC39") (pin "23") (pinfunction "A11_23") (pintype "input"))
    )
    (net (code "61") (name "MA1") (class "Default")
      (node (ref "IC19") (pin "6") (pinfunction "3Q_6") (pintype "tri_state"))
      (node (ref "IC38") (pin "21") (pinfunction "A10_21") (pintype "input"))
      (node (ref "IC39") (pin "21") (pinfunction "A10_21") (pintype "input"))
    )
    (net (code "62") (name "MA2") (class "Default")
      (node (ref "IC19") (pin "5") (pinfunction "2Q_5") (pintype "tri_state"))
      (node (ref "IC38") (pin "24") (pinfunction "A9_24") (pintype "input"))
      (node (ref "IC39") (pin "24") (pinfunction "A9_24") (pintype "input"))
    )
    (net (code "63") (name "MA3") (class "Default")
      (node (ref "IC19") (pin "2") (pinfunction "1Q_2") (pintype "tri_state"))
      (node (ref "IC38") (pin "25") (pinfunction "A8_25") (pintype "input"))
      (node (ref "IC39") (pin "25") (pinfunction "A8_25") (pintype "input"))
    )
    (net (code "64") (name "MA4") (class "Default")
      (node (ref "IC38") (pin "3") (pinfunction "A7_3") (pintype "input"))
      (node (ref "IC39") (pin "3") (pinfunction "A7_3") (pintype "input"))
      (node (ref "IC5") (pin "19") (pinfunction "8Q_19") (pintype "tri_state"))
    )
    (net (code "65") (name "MA5") (class "Default")
      (node (ref "IC38") (pin "4") (pinfunction "A6_4") (pintype "input"))
      (node (ref "IC39") (pin "4") (pinfunction "A6_4") (pintype "input"))
      (node (ref "IC5") (pin "16") (pinfunction "7Q_16") (pintype "tri_state"))
    )
    (net (code "66") (name "MA6") (class "Default")
      (node (ref "IC38") (pin "5") (pinfunction "A5_5") (pintype "input"))
      (node (ref "IC39") (pin "5") (pinfunction "A5_5") (pintype "input"))
      (node (ref "IC5") (pin "15") (pinfunction "6Q_15") (pintype "tri_state"))
    )
    (net (code "67") (name "MA7") (class "Default")
      (node (ref "IC38") (pin "6") (pinfunction "A4_6") (pintype "input"))
      (node (ref "IC39") (pin "6") (pinfunction "A4_6") (pintype "input"))
      (node (ref "IC5") (pin "12") (pinfunction "5Q_12") (pintype "tri_state"))
    )
    (net (code "68") (name "MA8") (class "Default")
      (node (ref "IC38") (pin "7") (pinfunction "A3_7") (pintype "input"))
      (node (ref "IC39") (pin "7") (pinfunction "A3_7") (pintype "input"))
      (node (ref "IC5") (pin "9") (pinfunction "4Q_9") (pintype "tri_state"))
    )
    (net (code "69") (name "MA9") (class "Default")
      (node (ref "IC38") (pin "8") (pinfunction "A2_8") (pintype "input"))
      (node (ref "IC39") (pin "8") (pinfunction "A2_8") (pintype "input"))
      (node (ref "IC5") (pin "6") (pinfunction "3Q_6") (pintype "tri_state"))
    )
    (net (code "70") (name "MA10") (class "Default")
      (node (ref "IC38") (pin "9") (pinfunction "A1_9") (pintype "input"))
      (node (ref "IC39") (pin "9") (pinfunction "A1_9") (pintype "input"))
      (node (ref "IC5") (pin "5") (pinfunction "2Q_5") (pintype "tri_state"))
    )
    (net (code "71") (name "MA11") (class "Default")
      (node (ref "IC38") (pin "10") (pinfunction "A0_10") (pintype "input"))
      (node (ref "IC39") (pin "10") (pinfunction "A0_10") (pintype "input"))
      (node (ref "IC5") (pin "2") (pinfunction "1Q_2") (pintype "tri_state"))
    )
    (net (code "72") (name "MEMDX0") (class "Default")
      (node (ref "IC15") (pin "1") (pinfunction "I0_1") (pintype "input"))
      (node (ref "IC39") (pin "15") (pinfunction "I/O3_15") (pintype "bidirectional"))
      (node (ref "IC9") (pin "18") (pinfunction "B1_18") (pintype "bidirectional"))
      (node (ref "SV1") (pin "35") (pinfunction "35_35") (pintype "passive"))
    )
    (net (code "73") (name "MEMDX1") (class "Default")
      (node (ref "IC3") (pin "6") (pinfunction "D3_6") (pintype "input"))
      (node (ref "IC39") (pin "13") (pinfunction "I/O2_13") (pintype "bidirectional"))
      (node (ref "IC9") (pin "17") (pinfunction "B2_17") (pintype "bidirectional"))
      (node (ref "SV1") (pin "33") (pinfunction "33_33") (pintype "passive"))
    )
    (net (code "74") (name "MEMDX2") (class "Default")
      (node (ref "IC3") (pin "3") (pinfunction "D2_3") (pintype "input"))
      (node (ref "IC39") (pin "12") (pinfunction "I/O1_12") (pintype "bidirectional"))
      (node (ref "IC9") (pin "16") (pinfunction "B3_16") (pintype "bidirectional"))
      (node (ref "SV1") (pin "31") (pinfunction "31_31") (pintype "passive"))
    )
    (net (code "75") (name "MEMDX3") (class "Default")
      (node (ref "IC3") (pin "2") (pinfunction "D1_2") (pintype "input"))
      (node (ref "IC39") (pin "11") (pinfunction "I/O0_11") (pintype "bidirectional"))
      (node (ref "IC9") (pin "11") (pinfunction "B8_11") (pintype "bidirectional"))
      (node (ref "SV1") (pin "29") (pinfunction "29_29") (pintype "passive"))
    )
    (net (code "76") (name "MEMDX4") (class "Default")
      (node (ref "IC2") (pin "7") (pinfunction "D4_7") (pintype "input"))
      (node (ref "IC38") (pin "19") (pinfunction "I/O7_19") (pintype "bidirectional"))
      (node (ref "IC6") (pin "11") (pinfunction "B8_11") (pintype "bidirectional"))
      (node (ref "SV1") (pin "27") (pinfunction "27_27") (pintype "passive"))
    )
    (net (code "77") (name "MEMDX5") (class "Default")
      (node (ref "IC2") (pin "6") (pinfunction "D3_6") (pintype "input"))
      (node (ref "IC38") (pin "18") (pinfunction "I/O6_18") (pintype "bidirectional"))
      (node (ref "IC6") (pin "12") (pinfunction "B7_12") (pintype "bidirectional"))
      (node (ref "SV1") (pin "25") (pinfunction "25_25") (pintype "passive"))
    )
    (net (code "78") (name "MEMDX6") (class "Default")
      (node (ref "IC2") (pin "3") (pinfunction "D2_3") (pintype "input"))
      (node (ref "IC38") (pin "17") (pinfunction "I/O5_17") (pintype "bidirectional"))
      (node (ref "IC6") (pin "13") (pinfunction "B6_13") (pintype "bidirectional"))
      (node (ref "SV1") (pin "23") (pinfunction "23_23") (pintype "passive"))
    )
    (net (code "79") (name "MEMDX7") (class "Default")
      (node (ref "IC2") (pin "2") (pinfunction "D1_2") (pintype "input"))
      (node (ref "IC38") (pin "16") (pinfunction "I/O4_16") (pintype "bidirectional"))
      (node (ref "IC6") (pin "14") (pinfunction "B5_14") (pintype "bidirectional"))
      (node (ref "SV1") (pin "21") (pinfunction "21_21") (pintype "passive"))
    )
    (net (code "80") (name "MEMDX8") (class "Default")
      (node (ref "IC1") (pin "7") (pinfunction "D4_7") (pintype "input"))
      (node (ref "IC38") (pin "15") (pinfunction "I/O3_15") (pintype "bidirectional"))
      (node (ref "IC6") (pin "15") (pinfunction "B4_15") (pintype "bidirectional"))
      (node (ref "SV1") (pin "19") (pinfunction "19_19") (pintype "passive"))
    )
    (net (code "81") (name "MEMDX9") (class "Default")
      (node (ref "IC1") (pin "6") (pinfunction "D3_6") (pintype "input"))
      (node (ref "IC38") (pin "13") (pinfunction "I/O2_13") (pintype "bidirectional"))
      (node (ref "IC6") (pin "16") (pinfunction "B3_16") (pintype "bidirectional"))
      (node (ref "SV1") (pin "17") (pinfunction "17_17") (pintype "passive"))
    )
    (net (code "82") (name "MEMDX10") (class "Default")
      (node (ref "IC1") (pin "3") (pinfunction "D2_3") (pintype "input"))
      (node (ref "IC38") (pin "12") (pinfunction "I/O1_12") (pintype "bidirectional"))
      (node (ref "IC6") (pin "17") (pinfunction "B2_17") (pintype "bidirectional"))
      (node (ref "SV1") (pin "15") (pinfunction "15_15") (pintype "passive"))
    )
    (net (code "83") (name "MEMDX11") (class "Default")
      (node (ref "IC1") (pin "2") (pinfunction "D1_2") (pintype "input"))
      (node (ref "IC38") (pin "11") (pinfunction "I/O0_11") (pintype "bidirectional"))
      (node (ref "IC6") (pin "18") (pinfunction "B1_18") (pintype "bidirectional"))
      (node (ref "SV1") (pin "13") (pinfunction "13_13") (pintype "passive"))
    )
    (net (code "84") (name "Net-(CPUA-OSCOUT)") (class "Default")
      (node (ref "CPU") (pin "14") (pinfunction "OSCOUT_14") (pintype "output"))
      (node (ref "QG1") (pin "5") (pinfunction "OUT_5") (pintype "output"))
      (node (ref "QG2") (pin "8") (pinfunction "OUT_8") (pintype "output"))
    )
    (net (code "85") (name "Net-(IC10D-O)") (class "Default")
      (node (ref "IC10") (pin "11") (pinfunction "O_11") (pintype "output"))
      (node (ref "IC20") (pin "3") (pinfunction "CLK_3") (pintype "input"))
    )
    (net (code "86") (name "Net-(IC11B-CLR)") (class "Default")
      (node (ref "IC11") (pin "13") (pinfunction "CLR_13") (pintype "input"))
      (node (ref "IC31") (pin "13") (pinfunction "CLR_13") (pintype "input"))
      (node (ref "IC40") (pin "12") (pinfunction "O_12") (pintype "output"))
    )
    (net (code "87") (name "Net-(IC11B-D)") (class "Default")
      (node (ref "IC11") (pin "12") (pinfunction "D_12") (pintype "input"))
      (node (ref "IC41") (pin "5") (pinfunction "Y_5") (pintype "output"))
    )
    (net (code "88") (name "Net-(IC15A-O)") (class "Default")
      (node (ref "IC15") (pin "3") (pinfunction "O_3") (pintype "output"))
      (node (ref "IC3") (pin "7") (pinfunction "D4_7") (pintype "input"))
    )
    (net (code "89") (name "Net-(IC15B-O)") (class "Default")
      (node (ref "IC1") (pin "13") (pinfunction "C12_13") (pintype "input"))
      (node (ref "IC1") (pin "4") (pinfunction "C34_4") (pintype "input"))
      (node (ref "IC15") (pin "6") (pinfunction "O_6") (pintype "output"))
      (node (ref "IC2") (pin "13") (pinfunction "C12_13") (pintype "input"))
      (node (ref "IC2") (pin "4") (pinfunction "C34_4") (pintype "input"))
      (node (ref "IC3") (pin "13") (pinfunction "C12_13") (pintype "input"))
      (node (ref "IC3") (pin "4") (pinfunction "C34_4") (pintype "input"))
    )
    (net (code "90") (name "Net-(IC15D-O)") (class "Default")
      (node (ref "IC15") (pin "11") (pinfunction "O_11") (pintype "output"))
      (node (ref "IC18") (pin "11") (pinfunction "CLK_11") (pintype "input"))
    )
    (net (code "91") (name "Net-(IC16B-O)") (class "Default")
      (node (ref "IC16") (pin "6") (pinfunction "O_6") (pintype "output"))
      (node (ref "IC21") (pin "1") (pinfunction "G_1") (pintype "input"))
    )
    (net (code "92") (name "Net-(IC16C-O)") (class "Default")
      (node (ref "IC16") (pin "8") (pinfunction "O_8") (pintype "output"))
      (node (ref "IC29") (pin "13") (pinfunction "I_13") (pintype "input"))
    )
    (net (code "93") (name "Net-(IC17A-O)") (class "Default")
      (node (ref "IC17") (pin "3") (pinfunction "O_3") (pintype "output"))
      (node (ref "IC17") (pin "4") (pinfunction "I0_4") (pintype "input"))
      (node (ref "IC17") (pin "9") (pinfunction "I0_9") (pintype "input"))
    )
    (net (code "94") (name "Net-(IC18A-PRE)") (class "Default")
      (node (ref "IC18") (pin "4") (pinfunction "PRE_4") (pintype "input"))
      (node (ref "IC23") (pin "6") (pinfunction "O_6") (pintype "output"))
    )
    (net (code "95") (name "Net-(IC22B-O)") (class "Default")
      (node (ref "IC22") (pin "8") (pinfunction "O_8") (pintype "output"))
      (node (ref "IC23") (pin "4") (pinfunction "I0_4") (pintype "input"))
      (node (ref "IC23") (pin "5") (pinfunction "I1_5") (pintype "input"))
    )
    (net (code "96") (name "Net-(IC24A-CLR)") (class "Default")
      (node (ref "IC24") (pin "15") (pinfunction "CLR_15") (pintype "input"))
      (node (ref "IC25") (pin "15") (pinfunction "CLR_15") (pintype "input"))
      (node (ref "IC26") (pin "6") (pinfunction "O_6") (pintype "output"))
      (node (ref "IC28") (pin "15") (pinfunction "CLR_15") (pintype "input"))
    )
    (net (code "97") (name "Net-(IC27A-G)") (class "Default")
      (node (ref "IC27") (pin "19") (pinfunction "G_19") (pintype "input"))
      (node (ref "IC30") (pin "19") (pinfunction "G_19") (pintype "input"))
      (node (ref "IC35") (pin "6") (pinfunction "O_6") (pintype "output"))
    )
    (net (code "98") (name "Net-(IC29E-I)") (class "Default")
      (node (ref "IC29") (pin "11") (pinfunction "I_11") (pintype "input"))
      (node (ref "IC31") (pin "5") (pinfunction "Q_5") (pintype "output"))
    )
    (net (code "99") (name "Net-(IC31A-CLR)") (class "Default")
      (node (ref "IC31") (pin "1") (pinfunction "CLR_1") (pintype "input"))
      (node (ref "IC35") (pin "11") (pinfunction "O_11") (pintype "output"))
    )
    (net (code "100") (name "Net-(IC32A-A4)") (class "Default")
      (node (ref "IC32") (pin "5") (pinfunction "A4_5") (pintype "bidirectional"))
      (node (ref "IC34") (pin "4") (pinfunction "1Y_4") (pintype "output"))
    )
    (net (code "101") (name "Net-(IC32A-A5)") (class "Default")
      (node (ref "IC32") (pin "6") (pinfunction "A5_6") (pintype "bidirectional"))
      (node (ref "IC34") (pin "7") (pinfunction "2Y_7") (pintype "output"))
    )
    (net (code "102") (name "Net-(IC32A-A6)") (class "Default")
      (node (ref "IC32") (pin "7") (pinfunction "A6_7") (pintype "bidirectional"))
      (node (ref "IC34") (pin "9") (pinfunction "3Y_9") (pintype "output"))
    )
    (net (code "103") (name "Net-(IC32A-G)") (class "Default")
      (node (ref "IC32") (pin "19") (pinfunction "G_19") (pintype "input"))
      (node (ref "IC35") (pin "3") (pinfunction "O_3") (pintype "output"))
      (node (ref "IC36") (pin "5") (pinfunction "I1_5") (pintype "input"))
    )
    (net (code "104") (name "Net-(IC33A-G)") (class "Default")
      (node (ref "IC33") (pin "19") (pinfunction "G_19") (pintype "input"))
      (node (ref "IC36") (pin "6") (pinfunction "O_6") (pintype "output"))
    )
    (net (code "105") (name "Net-(IC35A-I0)") (class "Default")
      (node (ref "IC35") (pin "1") (pinfunction "I0_1") (pintype "input"))
      (node (ref "IC36") (pin "3") (pinfunction "O_3") (pintype "output"))
    )
    (net (code "106") (name "Net-(IC35C-O)") (class "Default")
      (node (ref "IC35") (pin "8") (pinfunction "O_8") (pintype "output"))
      (node (ref "IC36") (pin "4") (pinfunction "I0_4") (pintype "input"))
      (node (ref "IC37") (pin "19") (pinfunction "G_19") (pintype "input"))
    )
    (net (code "107") (name "Net-(QG1-TS)") (class "Default")
      (node (ref "QG1") (pin "1") (pinfunction "TS_1") (pintype "passive"))
      (node (ref "QG2") (pin "1") (pinfunction "TS_1") (pintype "passive"))
    )
    (net (code "108") (name "POPR") (class "Default")
      (node (ref "IC10") (pin "2") (pinfunction "I1_2") (pintype "input"))
      (node (ref "IC8") (pin "6") (pinfunction "O_6") (pintype "output"))
    )
    (net (code "109") (name "RUN") (class "Default")
      (node (ref "CPU") (pin "2") (pinfunction "RUN_2") (pintype "output"))
      (node (ref "PAD6") (pin "1") (pinfunction "P_1") (pintype "passive"))
    )
    (net (code "110") (name "SF0") (class "Default")
      (node (ref "IC37") (pin "8") (pinfunction "A7_8") (pintype "bidirectional"))
      (node (ref "IC41") (pin "14") (pinfunction "D5_14") (pintype "input"))
      (node (ref "IC42") (pin "16") (pinfunction "Q7_16") (pintype "output"))
    )
    (net (code "111") (name "SF1") (class "Default")
      (node (ref "IC37") (pin "7") (pinfunction "A6_7") (pintype "bidirectional"))
      (node (ref "IC42") (pin "15") (pinfunction "Q6_15") (pintype "output"))
      (node (ref "IC48") (pin "6") (pinfunction "A3_6") (pintype "input"))
    )
    (net (code "112") (name "SF2") (class "Default")
      (node (ref "IC37") (pin "6") (pinfunction "A5_6") (pintype "bidirectional"))
      (node (ref "IC42") (pin "12") (pinfunction "Q5_12") (pintype "output"))
      (node (ref "IC48") (pin "4") (pinfunction "A2_4") (pintype "input"))
    )
    (net (code "113") (name "SF3") (class "Default")
      (node (ref "IC37") (pin "5") (pinfunction "A4_5") (pintype "bidirectional"))
      (node (ref "IC42") (pin "9") (pinfunction "Q4_9") (pintype "output"))
      (node (ref "IC48") (pin "2") (pinfunction "A1_2") (pintype "input"))
    )
    (net (code "114") (name "SF4") (class "Default")
      (node (ref "IC37") (pin "4") (pinfunction "A3_4") (pintype "bidirectional"))
      (node (ref "IC42") (pin "6") (pinfunction "Q3_6") (pintype "output"))
      (node (ref "IC48") (pin "15") (pinfunction "A3_15") (pintype "input"))
    )
    (net (code "115") (name "SF5") (class "Default")
      (node (ref "IC37") (pin "3") (pinfunction "A2_3") (pintype "bidirectional"))
      (node (ref "IC42") (pin "5") (pinfunction "Q2_5") (pintype "output"))
      (node (ref "IC48") (pin "13") (pinfunction "A2_13") (pintype "input"))
    )
    (net (code "116") (name "SF6") (class "Default")
      (node (ref "IC37") (pin "2") (pinfunction "A1_2") (pintype "bidirectional"))
      (node (ref "IC42") (pin "2") (pinfunction "Q1_2") (pintype "output"))
      (node (ref "IC48") (pin "11") (pinfunction "A1_11") (pintype "input"))
    )
    (net (code "117") (name "UB") (class "Default")
      (node (ref "IC11") (pin "9") (pinfunction "Q_9") (pintype "output"))
      (node (ref "IC31") (pin "12") (pinfunction "D_12") (pintype "input"))
      (node (ref "IC41") (pin "1") (pinfunction "D3_1") (pintype "input"))
      (node (ref "IC41") (pin "12") (pinfunction "D7_12") (pintype "input"))
      (node (ref "IC41") (pin "15") (pinfunction "D4_15") (pintype "input"))
      (node (ref "IC41") (pin "2") (pinfunction "D2_2") (pintype "input"))
      (node (ref "IC41") (pin "3") (pinfunction "D1_3") (pintype "input"))
      (node (ref "IC41") (pin "4") (pinfunction "D0_4") (pintype "input"))
    )
    (net (code "118") (name "USER_MODE") (class "Default")
      (node (ref "IC10") (pin "1") (pinfunction "I0_1") (pintype "input"))
      (node (ref "IC27") (pin "8") (pinfunction "A7_8") (pintype "bidirectional"))
      (node (ref "IC31") (pin "9") (pinfunction "Q_9") (pintype "output"))
      (node (ref "IC42") (pin "17") (pinfunction "D7_17") (pintype "input"))
    )
    (net (code "119") (name "VCC") (class "Default")
      (node (ref "IC12") (pin "1") (pinfunction "I0_1") (pintype "input"))
      (node (ref "IC12") (pin "2") (pinfunction "I1_2") (pintype "input"))
      (node (ref "IC13") (pin "6") (pinfunction "G1_6") (pintype "input"))
      (node (ref "IC17") (pin "12") (pinfunction "I0_12") (pintype "input"))
      (node (ref "IC17") (pin "13") (pinfunction "I1_13") (pintype "input"))
      (node (ref "IC20") (pin "10") (pinfunction "PRE_10") (pintype "input"))
      (node (ref "IC20") (pin "11") (pinfunction "CLK_11") (pintype "input"))
      (node (ref "IC20") (pin "12") (pinfunction "D_12") (pintype "input"))
      (node (ref "IC20") (pin "13") (pinfunction "CLR_13") (pintype "input"))
      (node (ref "IC20") (pin "2") (pinfunction "D_2") (pintype "input"))
      (node (ref "IC20") (pin "4") (pinfunction "PRE_4") (pintype "input"))
      (node (ref "IC22") (pin "1") (pinfunction "I0_1") (pintype "input"))
      (node (ref "IC23") (pin "12") (pinfunction "I0_12") (pintype "input"))
      (node (ref "IC23") (pin "13") (pinfunction "I1_13") (pintype "input"))
      (node (ref "IC27") (pin "1") (pinfunction "DIR_1") (pintype "input"))
      (node (ref "IC30") (pin "1") (pinfunction "DIR_1") (pintype "input"))
      (node (ref "IC31") (pin "10") (pinfunction "PRE_10") (pintype "input"))
      (node (ref "IC31") (pin "2") (pinfunction "D_2") (pintype "input"))
      (node (ref "IC31") (pin "4") (pinfunction "PRE_4") (pintype "input"))
      (node (ref "IC32") (pin "1") (pinfunction "DIR_1") (pintype "input"))
      (node (ref "IC33") (pin "1") (pinfunction "DIR_1") (pintype "input"))
      (node (ref "IC37") (pin "1") (pinfunction "DIR_1") (pintype "input"))
      (node (ref "IC38") (pin "28") (pinfunction "VCC_28") (pintype "power_in"))
      (node (ref "IC39") (pin "28") (pinfunction "VCC_28") (pintype "power_in"))
      (node (ref "IC7") (pin "6") (pinfunction "G1_6") (pintype "input"))
      (node (ref "IC8") (pin "9") (pinfunction "I0_9") (pintype "input"))
      (node (ref "QG1") (pin "8") (pinfunction "VCC_8") (pintype "power_in"))
      (node (ref "QG2") (pin "14") (pinfunction "VCC_14") (pintype "power_in"))
      (node (ref "RN4") (pin "1") (pinfunction "1_1") (pintype "passive"))
      (node (ref "SV1") (pin "1") (pinfunction "1_1") (pintype "passive"))
      (node (ref "SV1") (pin "3") (pinfunction "3_3") (pintype "passive"))
    )
    (net (code "120") (name "WASMEM") (class "Default")
      (node (ref "IC20") (pin "5") (pinfunction "Q_5") (pintype "output"))
      (node (ref "IC22") (pin "2") (pinfunction "I1_2") (pintype "input"))
    )
    (net (code "121") (name "XTA") (class "Default")
      (node (ref "CPU") (pin "9") (pinfunction "XTA_9") (pintype "output"))
      (node (ref "IC15") (pin "5") (pinfunction "I1_5") (pintype "input"))
      (node (ref "IC26") (pin "10") (pinfunction "I1_10") (pintype "input"))
      (node (ref "IC26") (pin "9") (pinfunction "I0_9") (pintype "input"))
      (node (ref "SV1") (pin "10") (pinfunction "10_10") (pintype "passive"))
    )
    (net (code "122") (name "XTB") (class "Default")
      (node (ref "CPU") (pin "12") (pinfunction "XTB_12") (pintype "output"))
      (node (ref "IC11") (pin "11") (pinfunction "CLK_11") (pintype "input"))
      (node (ref "IC26") (pin "12") (pinfunction "I0_12") (pintype "input"))
      (node (ref "IC26") (pin "13") (pinfunction "I1_13") (pintype "input"))
      (node (ref "IC41") (pin "9") (pinfunction "C_9") (pintype "input"))
      (node (ref "IC6") (pin "1") (pinfunction "DIR_1") (pintype "input"))
      (node (ref "IC9") (pin "1") (pinfunction "DIR_1") (pintype "input"))
      (node (ref "SV1") (pin "12") (pinfunction "12_12") (pintype "passive"))
    )
    (net (code "123") (name "XTC") (class "Default")
      (node (ref "CPU") (pin "13") (pinfunction "XTC_13") (pintype "output"))
      (node (ref "SV1") (pin "14") (pinfunction "14_14") (pintype "passive"))
    )
    (net (code "124") (name "ZF") (class "Default")
      (node (ref "IC16") (pin "5") (pinfunction "I1_5") (pintype "input"))
      (node (ref "IC18") (pin "9") (pinfunction "Q_9") (pintype "output"))
    )
    (net (code "125") (name "unconnected-(IC1A-~{Q3}-Pad11)") (class "Default")
      (node (ref "IC1") (pin "11") (pinfunction "~{Q3}_11") (pintype "output"))
    )
    (net (code "126") (name "unconnected-(IC2A-Q3-Pad10)") (class "Default")
      (node (ref "IC2") (pin "10") (pinfunction "Q3_10") (pintype "output"))
    )
    (net (code "127") (name "unconnected-(IC3A-~{Q2}-Pad14)") (class "Default")
      (node (ref "IC3") (pin "14") (pinfunction "~{Q2}_14") (pintype "output"))
    )
    (net (code "128") (name "unconnected-(IC3A-~{Q3}-Pad11)") (class "Default")
      (node (ref "IC3") (pin "11") (pinfunction "~{Q3}_11") (pintype "output"))
    )
    (net (code "129") (name "unconnected-(IC3A-~{Q4}-Pad8)") (class "Default")
      (node (ref "IC3") (pin "8") (pinfunction "~{Q4}_8") (pintype "output"))
    )
    (net (code "130") (name "unconnected-(IC4A-Y0-Pad15)") (class "Default")
      (node (ref "IC4") (pin "15") (pinfunction "Y0_15") (pintype "output"))
    )
    (net (code "131") (name "unconnected-(IC4A-Y1-Pad14)") (class "Default")
      (node (ref "IC4") (pin "14") (pinfunction "Y1_14") (pintype "output"))
    )
    (net (code "132") (name "unconnected-(IC4A-Y3-Pad12)") (class "Default")
      (node (ref "IC4") (pin "12") (pinfunction "Y3_12") (pintype "output"))
    )
    (net (code "133") (name "unconnected-(IC4A-Y5-Pad10)") (class "Default")
      (node (ref "IC4") (pin "10") (pinfunction "Y5_10") (pintype "output"))
    )
    (net (code "134") (name "unconnected-(IC4A-Y7-Pad7)") (class "Default")
      (node (ref "IC4") (pin "7") (pinfunction "Y7_7") (pintype "output"))
    )
    (net (code "135") (name "unconnected-(IC9A-A4-Pad5)") (class "Default")
      (node (ref "IC9") (pin "5") (pinfunction "A4_5") (pintype "bidirectional"))
    )
    (net (code "136") (name "unconnected-(IC9A-A5-Pad6)") (class "Default")
      (node (ref "IC9") (pin "6") (pinfunction "A5_6") (pintype "bidirectional"))
    )
    (net (code "137") (name "unconnected-(IC9A-A6-Pad7)") (class "Default")
      (node (ref "IC9") (pin "7") (pinfunction "A6_7") (pintype "bidirectional"))
    )
    (net (code "138") (name "unconnected-(IC9A-A7-Pad8)") (class "Default")
      (node (ref "IC9") (pin "8") (pinfunction "A7_8") (pintype "bidirectional"))
    )
    (net (code "139") (name "unconnected-(IC9A-B4-Pad15)") (class "Default")
      (node (ref "IC9") (pin "15") (pinfunction "B4_15") (pintype "bidirectional"))
    )
    (net (code "140") (name "unconnected-(IC9A-B5-Pad14)") (class "Default")
      (node (ref "IC9") (pin "14") (pinfunction "B5_14") (pintype "bidirectional"))
    )
    (net (code "141") (name "unconnected-(IC9A-B6-Pad13)") (class "Default")
      (node (ref "IC9") (pin "13") (pinfunction "B6_13") (pintype "bidirectional"))
    )
    (net (code "142") (name "unconnected-(IC9A-B7-Pad12)") (class "Default")
      (node (ref "IC9") (pin "12") (pinfunction "B7_12") (pintype "bidirectional"))
    )
    (net (code "143") (name "unconnected-(IC11A-Q-Pad5)") (class "Default")
      (node (ref "IC11") (pin "5") (pinfunction "Q_5") (pintype "output"))
    )
    (net (code "144") (name "unconnected-(IC11B-~{Q}-Pad8)") (class "Default")
      (node (ref "IC11") (pin "8") (pinfunction "~{Q}_8") (pintype "output"))
    )
    (net (code "145") (name "unconnected-(IC13A-Y0-Pad15)") (class "Default")
      (node (ref "IC13") (pin "15") (pinfunction "Y0_15") (pintype "output"))
    )
    (net (code "146") (name "unconnected-(IC13A-Y1-Pad14)") (class "Default")
      (node (ref "IC13") (pin "14") (pinfunction "Y1_14") (pintype "output"))
    )
    (net (code "147") (name "unconnected-(IC13A-Y2-Pad13)") (class "Default")
      (node (ref "IC13") (pin "13") (pinfunction "Y2_13") (pintype "output"))
    )
    (net (code "148") (name "unconnected-(IC13A-Y3-Pad12)") (class "Default")
      (node (ref "IC13") (pin "12") (pinfunction "Y3_12") (pintype "output"))
    )
    (net (code "149") (name "unconnected-(IC13A-Y6-Pad9)") (class "Default")
      (node (ref "IC13") (pin "9") (pinfunction "Y6_9") (pintype "output"))
    )
    (net (code "150") (name "unconnected-(IC17D-O-Pad11)") (class "Default")
      (node (ref "IC17") (pin "11") (pinfunction "O_11") (pintype "output"))
    )
    (net (code "151") (name "unconnected-(IC18A-~{Q}-Pad6)") (class "Default")
      (node (ref "IC18") (pin "6") (pinfunction "~{Q}_6") (pintype "output"))
    )
    (net (code "152") (name "unconnected-(IC18B-~{Q}-Pad8)") (class "Default")
      (node (ref "IC18") (pin "8") (pinfunction "~{Q}_8") (pintype "output"))
    )
    (net (code "153") (name "unconnected-(IC19A-8Q-Pad19)") (class "Default")
      (node (ref "IC19") (pin "19") (pinfunction "8Q_19") (pintype "tri_state"))
    )
    (net (code "154") (name "unconnected-(IC20A-~{Q}-Pad6)") (class "Default")
      (node (ref "IC20") (pin "6") (pinfunction "~{Q}_6") (pintype "output"))
    )
    (net (code "155") (name "unconnected-(IC20B-Q-Pad9)") (class "Default")
      (node (ref "IC20") (pin "9") (pinfunction "Q_9") (pintype "output"))
    )
    (net (code "156") (name "unconnected-(IC20B-~{Q}-Pad8)") (class "Default")
      (node (ref "IC20") (pin "8") (pinfunction "~{Q}_8") (pintype "output"))
    )
    (net (code "157") (name "unconnected-(IC21A-Y4-Pad12)") (class "Default")
      (node (ref "IC21") (pin "12") (pinfunction "Y4_12") (pintype "tri_state"))
    )
    (net (code "158") (name "unconnected-(IC21B-Y4-Pad3)") (class "Default")
      (node (ref "IC21") (pin "3") (pinfunction "Y4_3") (pintype "tri_state"))
    )
    (net (code "159") (name "unconnected-(IC23D-O-Pad11)") (class "Default")
      (node (ref "IC23") (pin "11") (pinfunction "O_11") (pintype "output"))
    )
    (net (code "160") (name "unconnected-(IC24A-Q4-Pad6)") (class "Default")
      (node (ref "IC24") (pin "6") (pinfunction "Q4_6") (pintype "tri_state"))
    )
    (net (code "161") (name "unconnected-(IC25A-Q4-Pad6)") (class "Default")
      (node (ref "IC25") (pin "6") (pinfunction "Q4_6") (pintype "tri_state"))
    )
    (net (code "162") (name "unconnected-(IC28A-Q4-Pad6)") (class "Default")
      (node (ref "IC28") (pin "6") (pinfunction "Q4_6") (pintype "tri_state"))
    )
    (net (code "163") (name "unconnected-(IC30A-B5-Pad14)") (class "Default")
      (node (ref "IC30") (pin "14") (pinfunction "B5_14") (pintype "bidirectional"))
    )
    (net (code "164") (name "unconnected-(IC30A-B6-Pad13)") (class "Default")
      (node (ref "IC30") (pin "13") (pinfunction "B6_13") (pintype "bidirectional"))
    )
    (net (code "165") (name "unconnected-(IC30A-B7-Pad12)") (class "Default")
      (node (ref "IC30") (pin "12") (pinfunction "B7_12") (pintype "bidirectional"))
    )
    (net (code "166") (name "unconnected-(IC30A-B8-Pad11)") (class "Default")
      (node (ref "IC30") (pin "11") (pinfunction "B8_11") (pintype "bidirectional"))
    )
    (net (code "167") (name "unconnected-(IC31A-~{Q}-Pad6)") (class "Default")
      (node (ref "IC31") (pin "6") (pinfunction "~{Q}_6") (pintype "output"))
    )
    (net (code "168") (name "unconnected-(IC31B-~{Q}-Pad8)") (class "Default")
      (node (ref "IC31") (pin "8") (pinfunction "~{Q}_8") (pintype "output"))
    )
    (net (code "169") (name "unconnected-(IC33A-B5-Pad14)") (class "Default")
      (node (ref "IC33") (pin "14") (pinfunction "B5_14") (pintype "bidirectional"))
    )
    (net (code "170") (name "unconnected-(IC33A-B6-Pad13)") (class "Default")
      (node (ref "IC33") (pin "13") (pinfunction "B6_13") (pintype "bidirectional"))
    )
    (net (code "171") (name "unconnected-(IC33A-B7-Pad12)") (class "Default")
      (node (ref "IC33") (pin "12") (pinfunction "B7_12") (pintype "bidirectional"))
    )
    (net (code "172") (name "unconnected-(IC33A-B8-Pad11)") (class "Default")
      (node (ref "IC33") (pin "11") (pinfunction "B8_11") (pintype "bidirectional"))
    )
    (net (code "173") (name "unconnected-(IC34A-4Y-Pad12)") (class "Default")
      (node (ref "IC34") (pin "12") (pinfunction "4Y_12") (pintype "output"))
    )
    (net (code "174") (name "unconnected-(IC39-I{slash}O4-Pad16)") (class "Default")
      (node (ref "IC39") (pin "16") (pinfunction "I/O4_16") (pintype "bidirectional"))
    )
    (net (code "175") (name "unconnected-(IC39-I{slash}O5-Pad17)") (class "Default")
      (node (ref "IC39") (pin "17") (pinfunction "I/O5_17") (pintype "bidirectional"))
    )
    (net (code "176") (name "unconnected-(IC39-I{slash}O6-Pad18)") (class "Default")
      (node (ref "IC39") (pin "18") (pinfunction "I/O6_18") (pintype "bidirectional"))
    )
    (net (code "177") (name "unconnected-(IC39-I{slash}O7-Pad19)") (class "Default")
      (node (ref "IC39") (pin "19") (pinfunction "I/O7_19") (pintype "bidirectional"))
    )
    (net (code "178") (name "unconnected-(IC41A-W-Pad6)") (class "Default")
      (node (ref "IC41") (pin "6") (pinfunction "W_6") (pintype "output"))
    )
    (net (code "179") (name "unconnected-(IC42A-Q8-Pad19)") (class "Default")
      (node (ref "IC42") (pin "19") (pinfunction "Q8_19") (pintype "output"))
    )
    (net (code "180") (name "unconnected-(IC46A-Y4-Pad12)") (class "Default")
      (node (ref "IC46") (pin "12") (pinfunction "Y4_12") (pintype "tri_state"))
    )
    (net (code "181") (name "unconnected-(IC46B-Y4-Pad3)") (class "Default")
      (node (ref "IC46") (pin "3") (pinfunction "Y4_3") (pintype "tri_state"))
    )
    (net (code "182") (name "unconnected-(IC47A-Y4-Pad12)") (class "Default")
      (node (ref "IC47") (pin "12") (pinfunction "Y4_12") (pintype "tri_state"))
    )
    (net (code "183") (name "unconnected-(IC47B-Y4-Pad3)") (class "Default")
      (node (ref "IC47") (pin "3") (pinfunction "Y4_3") (pintype "tri_state"))
    )
    (net (code "184") (name "unconnected-(IC48A-Y4-Pad12)") (class "Default")
      (node (ref "IC48") (pin "12") (pinfunction "Y4_12") (pintype "tri_state"))
    )
    (net (code "185") (name "unconnected-(IC48B-Y4-Pad3)") (class "Default")
      (node (ref "IC48") (pin "3") (pinfunction "Y4_3") (pintype "tri_state"))
    )
    (net (code "186") (name "unconnected-(SV1-Pad2)") (class "Default")
      (node (ref "SV1") (pin "2") (pinfunction "2_2") (pintype "passive"))
    )
    (net (code "187") (name "unconnected-(SV1-Pad4)") (class "Default")
      (node (ref "SV1") (pin "4") (pinfunction "4_4") (pintype "passive"))
    )
    (net (code "188") (name "unconnected-(SV1-Pad38)") (class "Default")
      (node (ref "SV1") (pin "38") (pinfunction "38_38") (pintype "passive"))
    )
    (net (code "189") (name "unconnected-(SV1-Pad40)") (class "Default")
      (node (ref "SV1") (pin "40") (pinfunction "40_40") (pintype "passive"))
    )
    (net (code "190") (name "~{00}") (class "Default")
      (node (ref "IC12") (pin "8") (pinfunction "O_8") (pintype "output"))
      (node (ref "IC13") (pin "4") (pinfunction "G2A_4") (pintype "input"))
    )
    (net (code "191") (name "~{2X}") (class "Default")
      (node (ref "IC14") (pin "4") (pinfunction "G2A_4") (pintype "input"))
      (node (ref "IC17") (pin "1") (pinfunction "I0_1") (pintype "input"))
      (node (ref "IC8") (pin "8") (pinfunction "O_8") (pintype "output"))
    )
    (net (code "192") (name "~{AND}") (class "Default")
      (node (ref "IC7") (pin "15") (pinfunction "Y0_15") (pintype "output"))
      (node (ref "PAD1") (pin "1") (pinfunction "P_1") (pintype "passive"))
    )
    (net (code "193") (name "~{C0}") (class "Default")
      (node (ref "CPU") (pin "32") (pinfunction "C0_32") (pintype "input"))
      (node (ref "RN4") (pin "7") (pinfunction "7_7") (pintype "passive"))
      (node (ref "SV1") (pin "18") (pinfunction "18_18") (pintype "passive"))
    )
    (net (code "194") (name "~{C1}") (class "Default")
      (node (ref "CPU") (pin "33") (pinfunction "C1_33") (pintype "input"))
      (node (ref "IC29") (pin "2") (pinfunction "O_2") (pintype "open_collector"))
      (node (ref "IC29") (pin "4") (pinfunction "O_4") (pintype "open_collector"))
      (node (ref "IC29") (pin "6") (pinfunction "O_6") (pintype "open_collector"))
      (node (ref "IC29") (pin "8") (pinfunction "O_8") (pintype "open_collector"))
      (node (ref "RN4") (pin "6") (pinfunction "6_6") (pintype "passive"))
      (node (ref "SV1") (pin "20") (pinfunction "20_20") (pintype "passive"))
    )
    (net (code "195") (name "~{C2}") (class "Default")
      (node (ref "CPU") (pin "34") (pinfunction "C2_34") (pintype "input"))
      (node (ref "RN4") (pin "5") (pinfunction "5_5") (pintype "passive"))
      (node (ref "SV1") (pin "22") (pinfunction "22_22") (pintype "passive"))
    )
    (net (code "196") (name "~{CAF}") (class "Default")
      (node (ref "IC13") (pin "7") (pinfunction "Y7_7") (pintype "output"))
      (node (ref "IC35") (pin "12") (pinfunction "I0_12") (pintype "input"))
    )
    (net (code "197") (name "~{CDF}") (class "Default")
      (node (ref "IC17") (pin "8") (pinfunction "O_8") (pintype "output"))
      (node (ref "IC40") (pin "10") (pinfunction "I1_10") (pintype "input"))
      (node (ref "IC47") (pin "17") (pinfunction "A4_17") (pintype "input"))
      (node (ref "IC47") (pin "19") (pinfunction "G_19") (pintype "input"))
    )
    (net (code "198") (name "~{CIF}") (class "Default")
      (node (ref "IC17") (pin "6") (pinfunction "O_6") (pintype "output"))
      (node (ref "IC22") (pin "10") (pinfunction "I1_10") (pintype "input"))
      (node (ref "IC40") (pin "4") (pinfunction "I1_4") (pintype "input"))
      (node (ref "IC47") (pin "1") (pinfunction "G_1") (pintype "input"))
    )
    (net (code "199") (name "~{CINT}") (class "Default")
      (node (ref "IC11") (pin "3") (pinfunction "CLK_3") (pintype "input"))
      (node (ref "IC14") (pin "15") (pinfunction "Y0_15") (pintype "output"))
    )
    (net (code "200") (name "~{CPREQ}") (class "Default")
      (node (ref "CPU") (pin "5") (pinfunction "CPREQ_5") (pintype "input"))
      (node (ref "SV1") (pin "36") (pinfunction "36_36") (pintype "passive"))
    )
    (net (code "201") (name "~{CPSEL}") (class "Default")
      (node (ref "CPU") (pin "38") (pinfunction "CPSEL_38") (pintype "output"))
      (node (ref "IC15") (pin "2") (pinfunction "I1_2") (pintype "input"))
      (node (ref "IC23") (pin "1") (pinfunction "I0_1") (pintype "input"))
      (node (ref "IC23") (pin "2") (pinfunction "I1_2") (pintype "input"))
    )
    (net (code "202") (name "~{CPUINTREQ}") (class "Default")
      (node (ref "CPU") (pin "8") (pinfunction "INTREQ_8") (pintype "input"))
      (node (ref "IC16") (pin "3") (pinfunction "O_3") (pintype "output"))
    )
    (net (code "203") (name "~{CUF}") (class "Default")
      (node (ref "IC14") (pin "9") (pinfunction "Y6_9") (pintype "output"))
      (node (ref "IC40") (pin "2") (pinfunction "I1_2") (pintype "input"))
    )
    (net (code "204") (name "~{DCA}") (class "Default")
      (node (ref "IC7") (pin "12") (pinfunction "Y3_12") (pintype "output"))
      (node (ref "PAD4") (pin "1") (pinfunction "P_1") (pintype "passive"))
    )
    (net (code "205") (name "~{DEVINTREQ}") (class "Default")
      (node (ref "IC16") (pin "1") (pinfunction "I0_1") (pintype "input"))
      (node (ref "IC23") (pin "10") (pinfunction "I1_10") (pintype "input"))
      (node (ref "IC23") (pin "9") (pinfunction "I0_9") (pintype "input"))
      (node (ref "SV1") (pin "8") (pinfunction "8_8") (pintype "passive"))
    )
    (net (code "206") (name "~{DEVSEL}") (class "Default")
      (node (ref "CPU") (pin "30") (pinfunction "DEVSEL_30") (pintype "output"))
      (node (ref "IC13") (pin "5") (pinfunction "G2B_5") (pintype "input"))
      (node (ref "IC14") (pin "5") (pinfunction "G2B_5") (pintype "input"))
      (node (ref "SV1") (pin "16") (pinfunction "16_16") (pintype "passive"))
    )
    (net (code "207") (name "~{DMAREQ}") (class "Default")
      (node (ref "CPU") (pin "4") (pinfunction "DMAREQ_4") (pintype "input"))
      (node (ref "SV1") (pin "7") (pinfunction "7_7") (pintype "passive"))
    )
    (net (code "208") (name "~{DORTF}") (class "Default")
      (node (ref "IC16") (pin "11") (pinfunction "O_11") (pintype "output"))
      (node (ref "IC40") (pin "3") (pinfunction "I0_3") (pintype "input"))
      (node (ref "IC40") (pin "9") (pinfunction "I0_9") (pintype "input"))
    )
    (net (code "209") (name "~{ERROR}") (class "Default")
      (node (ref "IC10") (pin "3") (pinfunction "O_3") (pintype "output"))
      (node (ref "IC10") (pin "4") (pinfunction "I0_4") (pintype "input"))
      (node (ref "IC10") (pin "5") (pinfunction "I1_5") (pintype "input"))
      (node (ref "IC11") (pin "4") (pinfunction "PRE_4") (pintype "input"))
    )
    (net (code "210") (name "~{GTF}") (class "Default")
      (node (ref "IC13") (pin "11") (pinfunction "Y4_11") (pintype "output"))
      (node (ref "IC29") (pin "1") (pinfunction "I_1") (pintype "input"))
      (node (ref "IC35") (pin "4") (pinfunction "I0_4") (pintype "input"))
    )
    (net (code "211") (name "~{HLT}") (class "Default")
      (node (ref "IC4") (pin "13") (pinfunction "Y2_13") (pintype "output"))
      (node (ref "IC8") (pin "1") (pinfunction "I0_1") (pintype "input"))
    )
    (net (code "212") (name "~{INTCLR}") (class "Default")
      (node (ref "IC26") (pin "3") (pinfunction "O_3") (pintype "output"))
      (node (ref "IC26") (pin "4") (pinfunction "I0_4") (pintype "input"))
      (node (ref "IC40") (pin "13") (pinfunction "I2_13") (pintype "input"))
    )
    (net (code "213") (name "~{IOT}") (class "Default")
      (node (ref "IC31") (pin "3") (pinfunction "CLK_3") (pintype "input"))
      (node (ref "IC7") (pin "9") (pinfunction "Y6_9") (pintype "output"))
      (node (ref "IC8") (pin "5") (pinfunction "I3_5") (pintype "input"))
    )
    (net (code "214") (name "~{IO_RESET}") (class "Default")
      (node (ref "IC29") (pin "10") (pinfunction "O_10") (pintype "open_collector"))
      (node (ref "SV1") (pin "11") (pinfunction "11_11") (pintype "passive"))
    )
    (net (code "215") (name "~{IR3}") (class "Default")
      (node (ref "IC12") (pin "12") (pinfunction "I7_12") (pintype "input"))
      (node (ref "IC3") (pin "1") (pinfunction "~{Q1}_1") (pintype "output"))
      (node (ref "IC8") (pin "13") (pinfunction "I3_13") (pintype "input"))
    )
    (net (code "216") (name "~{IR4}") (class "Default")
      (node (ref "IC12") (pin "11") (pinfunction "I6_11") (pintype "input"))
      (node (ref "IC2") (pin "8") (pinfunction "~{Q4}_8") (pintype "output"))
    )
    (net (code "217") (name "~{IR5}") (class "Default")
      (node (ref "IC12") (pin "6") (pinfunction "I5_6") (pintype "input"))
      (node (ref "IC2") (pin "11") (pinfunction "~{Q3}_11") (pintype "output"))
      (node (ref "IC8") (pin "10") (pinfunction "I1_10") (pintype "input"))
    )
    (net (code "218") (name "~{IR6}") (class "Default")
      (node (ref "IC12") (pin "5") (pinfunction "I4_5") (pintype "input"))
      (node (ref "IC2") (pin "14") (pinfunction "~{Q2}_14") (pintype "output"))
    )
    (net (code "219") (name "~{IR7}") (class "Default")
      (node (ref "IC12") (pin "4") (pinfunction "I3_4") (pintype "input"))
      (node (ref "IC2") (pin "1") (pinfunction "~{Q1}_1") (pintype "output"))
    )
    (net (code "220") (name "~{IR8}") (class "Default")
      (node (ref "IC1") (pin "8") (pinfunction "~{Q4}_8") (pintype "output"))
      (node (ref "IC12") (pin "3") (pinfunction "I2_3") (pintype "input"))
    )
    (net (code "221") (name "~{IR10}") (class "Default")
      (node (ref "IC1") (pin "14") (pinfunction "~{Q2}_14") (pintype "output"))
      (node (ref "IC17") (pin "5") (pinfunction "I1_5") (pintype "input"))
    )
    (net (code "222") (name "~{IR11}") (class "Default")
      (node (ref "IC1") (pin "1") (pinfunction "~{Q1}_1") (pintype "output"))
      (node (ref "IC17") (pin "10") (pinfunction "I1_10") (pintype "input"))
    )
    (net (code "223") (name "~{ISZ}") (class "Default")
      (node (ref "IC7") (pin "13") (pinfunction "Y2_13") (pintype "output"))
      (node (ref "PAD3") (pin "1") (pinfunction "P_1") (pintype "passive"))
    )
    (net (code "224") (name "~{JMP}") (class "Default")
      (node (ref "IC10") (pin "9") (pinfunction "I0_9") (pintype "input"))
      (node (ref "IC7") (pin "10") (pinfunction "Y5_10") (pintype "output"))
    )
    (net (code "225") (name "~{JMS}") (class "Default")
      (node (ref "IC10") (pin "10") (pinfunction "I1_10") (pintype "input"))
      (node (ref "IC7") (pin "11") (pinfunction "Y4_11") (pintype "output"))
    )
    (net (code "226") (name "~{MEMSEL}") (class "Default")
      (node (ref "CPU") (pin "37") (pinfunction "MEMSEL_37") (pintype "output"))
      (node (ref "IC10") (pin "13") (pinfunction "I1_13") (pintype "input"))
      (node (ref "IC36") (pin "12") (pinfunction "I0_12") (pintype "input"))
      (node (ref "IC36") (pin "9") (pinfunction "I0_9") (pintype "input"))
      (node (ref "IC38") (pin "20") (pinfunction "~{CS}_20") (pintype "input"))
      (node (ref "IC39") (pin "20") (pinfunction "~{CS}_20") (pintype "input"))
    )
    (net (code "227") (name "~{OE}") (class "Default")
      (node (ref "IC36") (pin "11") (pinfunction "O_11") (pintype "output"))
      (node (ref "IC38") (pin "22") (pinfunction "~{OE}_22") (pintype "input"))
      (node (ref "IC39") (pin "22") (pinfunction "~{OE}_22") (pintype "input"))
    )
    (net (code "228") (name "~{OPR}") (class "Default")
      (node (ref "IC4") (pin "4") (pinfunction "G2A_4") (pintype "input"))
      (node (ref "IC4") (pin "5") (pinfunction "G2B_5") (pintype "input"))
      (node (ref "IC7") (pin "7") (pinfunction "Y7_7") (pintype "output"))
    )
    (net (code "229") (name "~{OSRHLT}") (class "Default")
      (node (ref "IC4") (pin "9") (pinfunction "Y6_9") (pintype "output"))
      (node (ref "IC8") (pin "4") (pinfunction "I2_4") (pintype "input"))
    )
    (net (code "230") (name "~{OSR}") (class "Default")
      (node (ref "IC4") (pin "11") (pinfunction "Y4_11") (pintype "output"))
      (node (ref "IC8") (pin "2") (pinfunction "I1_2") (pintype "input"))
    )
    (net (code "231") (name "~{RDF}") (class "Default")
      (node (ref "IC14") (pin "14") (pinfunction "Y1_14") (pintype "output"))
      (node (ref "IC29") (pin "3") (pinfunction "I_3") (pintype "input"))
      (node (ref "IC36") (pin "2") (pinfunction "I1_2") (pintype "input"))
    )
    (net (code "232") (name "~{RESET}") (class "Default")
      (node (ref "CPU") (pin "7") (pinfunction "RESET_7") (pintype "input"))
      (node (ref "IC11") (pin "1") (pinfunction "CLR_1") (pintype "input"))
      (node (ref "IC18") (pin "1") (pinfunction "CLR_1") (pintype "input"))
      (node (ref "IC18") (pin "13") (pinfunction "CLR_13") (pintype "input"))
      (node (ref "IC26") (pin "5") (pinfunction "I1_5") (pintype "input"))
      (node (ref "IC35") (pin "13") (pinfunction "I1_13") (pintype "input"))
      (node (ref "IC40") (pin "1") (pinfunction "I0_1") (pintype "input"))
      (node (ref "IC42") (pin "1") (pinfunction "CLR_1") (pintype "input"))
      (node (ref "PAD7") (pin "1") (pinfunction "P_1") (pintype "passive"))
    )
    (net (code "233") (name "~{RIB}") (class "Default")
      (node (ref "IC14") (pin "12") (pinfunction "Y3_12") (pintype "output"))
      (node (ref "IC29") (pin "9") (pinfunction "I_9") (pintype "input"))
      (node (ref "IC35") (pin "9") (pinfunction "I0_9") (pintype "input"))
    )
    (net (code "234") (name "~{RIF}") (class "Default")
      (node (ref "IC14") (pin "13") (pinfunction "Y2_13") (pintype "output"))
      (node (ref "IC29") (pin "5") (pinfunction "I_5") (pintype "input"))
      (node (ref "IC34") (pin "1") (pinfunction "~{A}/B_1") (pintype "input"))
      (node (ref "IC36") (pin "1") (pinfunction "I0_1") (pintype "input"))
    )
    (net (code "235") (name "~{RMF}") (class "Default")
      (node (ref "IC14") (pin "11") (pinfunction "Y4_11") (pintype "output"))
      (node (ref "IC22") (pin "12") (pinfunction "I2_12") (pintype "input"))
      (node (ref "IC40") (pin "11") (pinfunction "I2_11") (pintype "input"))
      (node (ref "IC40") (pin "5") (pinfunction "I2_5") (pintype "input"))
      (node (ref "IC41") (pin "11") (pinfunction "A_11") (pintype "input"))
      (node (ref "IC48") (pin "1") (pinfunction "G_1") (pintype "input"))
      (node (ref "IC48") (pin "17") (pinfunction "A4_17") (pintype "input"))
      (node (ref "IC48") (pin "19") (pinfunction "G_19") (pintype "input"))
    )
    (net (code "236") (name "~{RTF}") (class "Default")
      (node (ref "IC13") (pin "10") (pinfunction "Y5_10") (pintype "output"))
      (node (ref "IC16") (pin "12") (pinfunction "I0_12") (pintype "input"))
      (node (ref "IC22") (pin "9") (pinfunction "I0_9") (pintype "input"))
      (node (ref "IC41") (pin "10") (pinfunction "B_10") (pintype "input"))
      (node (ref "IC46") (pin "1") (pinfunction "G_1") (pintype "input"))
      (node (ref "IC46") (pin "17") (pinfunction "A4_17") (pintype "input"))
      (node (ref "IC46") (pin "19") (pinfunction "G_19") (pintype "input"))
    )
    (net (code "237") (name "~{RUNHLT}") (class "Default")
      (node (ref "CPU") (pin "6") (pinfunction "RUNHLT_6") (pintype "input"))
      (node (ref "SV1") (pin "9") (pinfunction "9_9") (pintype "passive"))
    )
    (net (code "238") (name "~{SETZF}") (class "Default")
      (node (ref "IC18") (pin "10") (pinfunction "PRE_10") (pintype "input"))
      (node (ref "IC20") (pin "1") (pinfunction "CLR_1") (pintype "input"))
      (node (ref "IC22") (pin "6") (pinfunction "O_6") (pintype "output"))
    )
    (net (code "239") (name "~{SINT}") (class "Default")
      (node (ref "IC14") (pin "10") (pinfunction "Y5_10") (pintype "output"))
      (node (ref "IC16") (pin "9") (pinfunction "I0_9") (pintype "input"))
    )
    (net (code "240") (name "~{SKP}") (class "Default")
      (node (ref "CPU") (pin "35") (pinfunction "SKP_35") (pintype "input"))
      (node (ref "IC29") (pin "12") (pinfunction "O_12") (pintype "open_collector"))
      (node (ref "SV1") (pin "24") (pinfunction "24_24") (pintype "passive"))
    )
    (net (code "241") (name "~{SUF}") (class "Default")
      (node (ref "IC11") (pin "10") (pinfunction "PRE_10") (pintype "input"))
      (node (ref "IC14") (pin "7") (pinfunction "Y7_7") (pintype "output"))
      (node (ref "IC22") (pin "13") (pinfunction "I3_13") (pintype "input"))
    )
    (net (code "242") (name "~{SWSEL}") (class "Default")
      (node (ref "CPU") (pin "31") (pinfunction "SWSEL_31") (pintype "output"))
      (node (ref "PAD8") (pin "1") (pinfunction "P_1") (pintype "passive"))
    )
    (net (code "243") (name "~{TAD}") (class "Default")
      (node (ref "IC7") (pin "14") (pinfunction "Y1_14") (pintype "output"))
      (node (ref "PAD2") (pin "1") (pinfunction "P_1") (pintype "passive"))
    )
    (net (code "244") (name "~{UIF}") (class "Default")
      (node (ref "IC11") (pin "6") (pinfunction "~{Q}_6") (pintype "output"))
      (node (ref "IC16") (pin "10") (pinfunction "I1_10") (pintype "input"))
    )
    (net (code "245") (name "~{WAIT}") (class "Default")
      (node (ref "CPU") (pin "11") (pinfunction "WAIT_11") (pintype "input"))
      (node (ref "SV1") (pin "26") (pinfunction "26_26") (pintype "passive"))
    )
    (net (code "246") (name "~{WE}") (class "Default")
      (node (ref "IC36") (pin "8") (pinfunction "O_8") (pintype "output"))
      (node (ref "IC38") (pin "27") (pinfunction "~{WE}_27") (pintype "input"))
      (node (ref "IC39") (pin "27") (pinfunction "~{WE}_27") (pintype "input"))
    )
    (net (code "247") (name "~{XTA}") (class "Default")
      (node (ref "IC26") (pin "8") (pinfunction "O_8") (pintype "output"))
      (node (ref "IC35") (pin "10") (pinfunction "I1_10") (pintype "input"))
      (node (ref "IC35") (pin "2") (pinfunction "I1_2") (pintype "input"))
      (node (ref "IC35") (pin "5") (pinfunction "I1_5") (pintype "input"))
      (node (ref "IC36") (pin "13") (pinfunction "I1_13") (pintype "input"))
    )
    (net (code "248") (name "~{XTB}") (class "Default")
      (node (ref "IC16") (pin "13") (pinfunction "I1_13") (pintype "input"))
      (node (ref "IC26") (pin "11") (pinfunction "O_11") (pintype "output"))
      (node (ref "IC36") (pin "10") (pinfunction "I1_10") (pintype "input"))
    )
  )
)
